# BatteryBoardV3.net
KiCad netlist of a schematic drawn in EAGLE
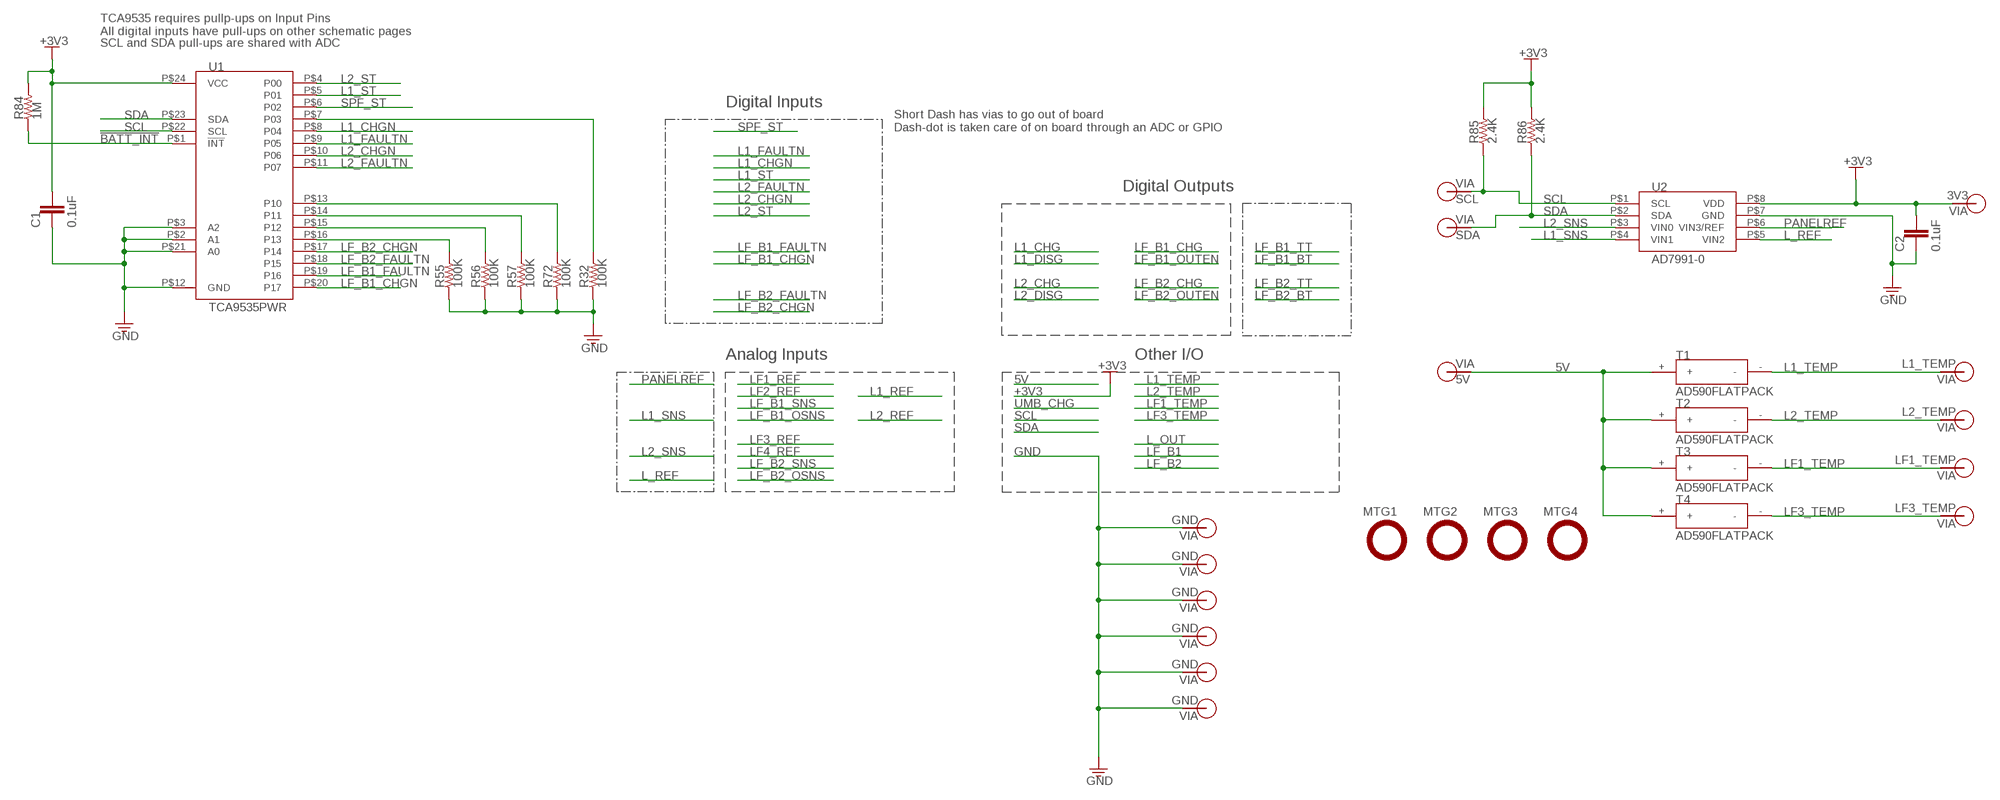
[diagram p0: schematic, sheet 1]
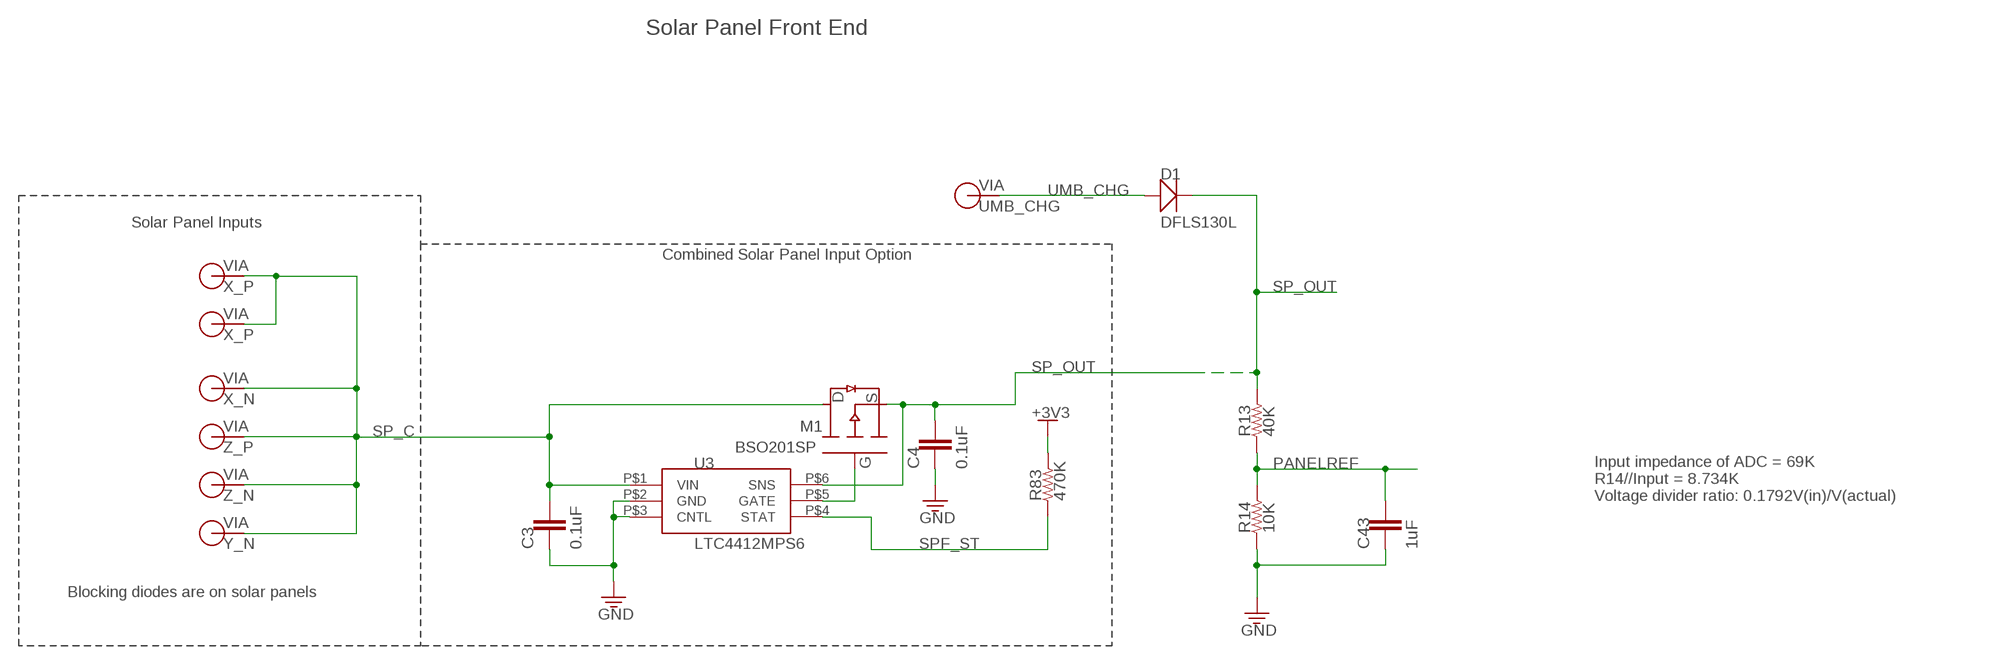
[diagram p1: schematic, sheet 2]
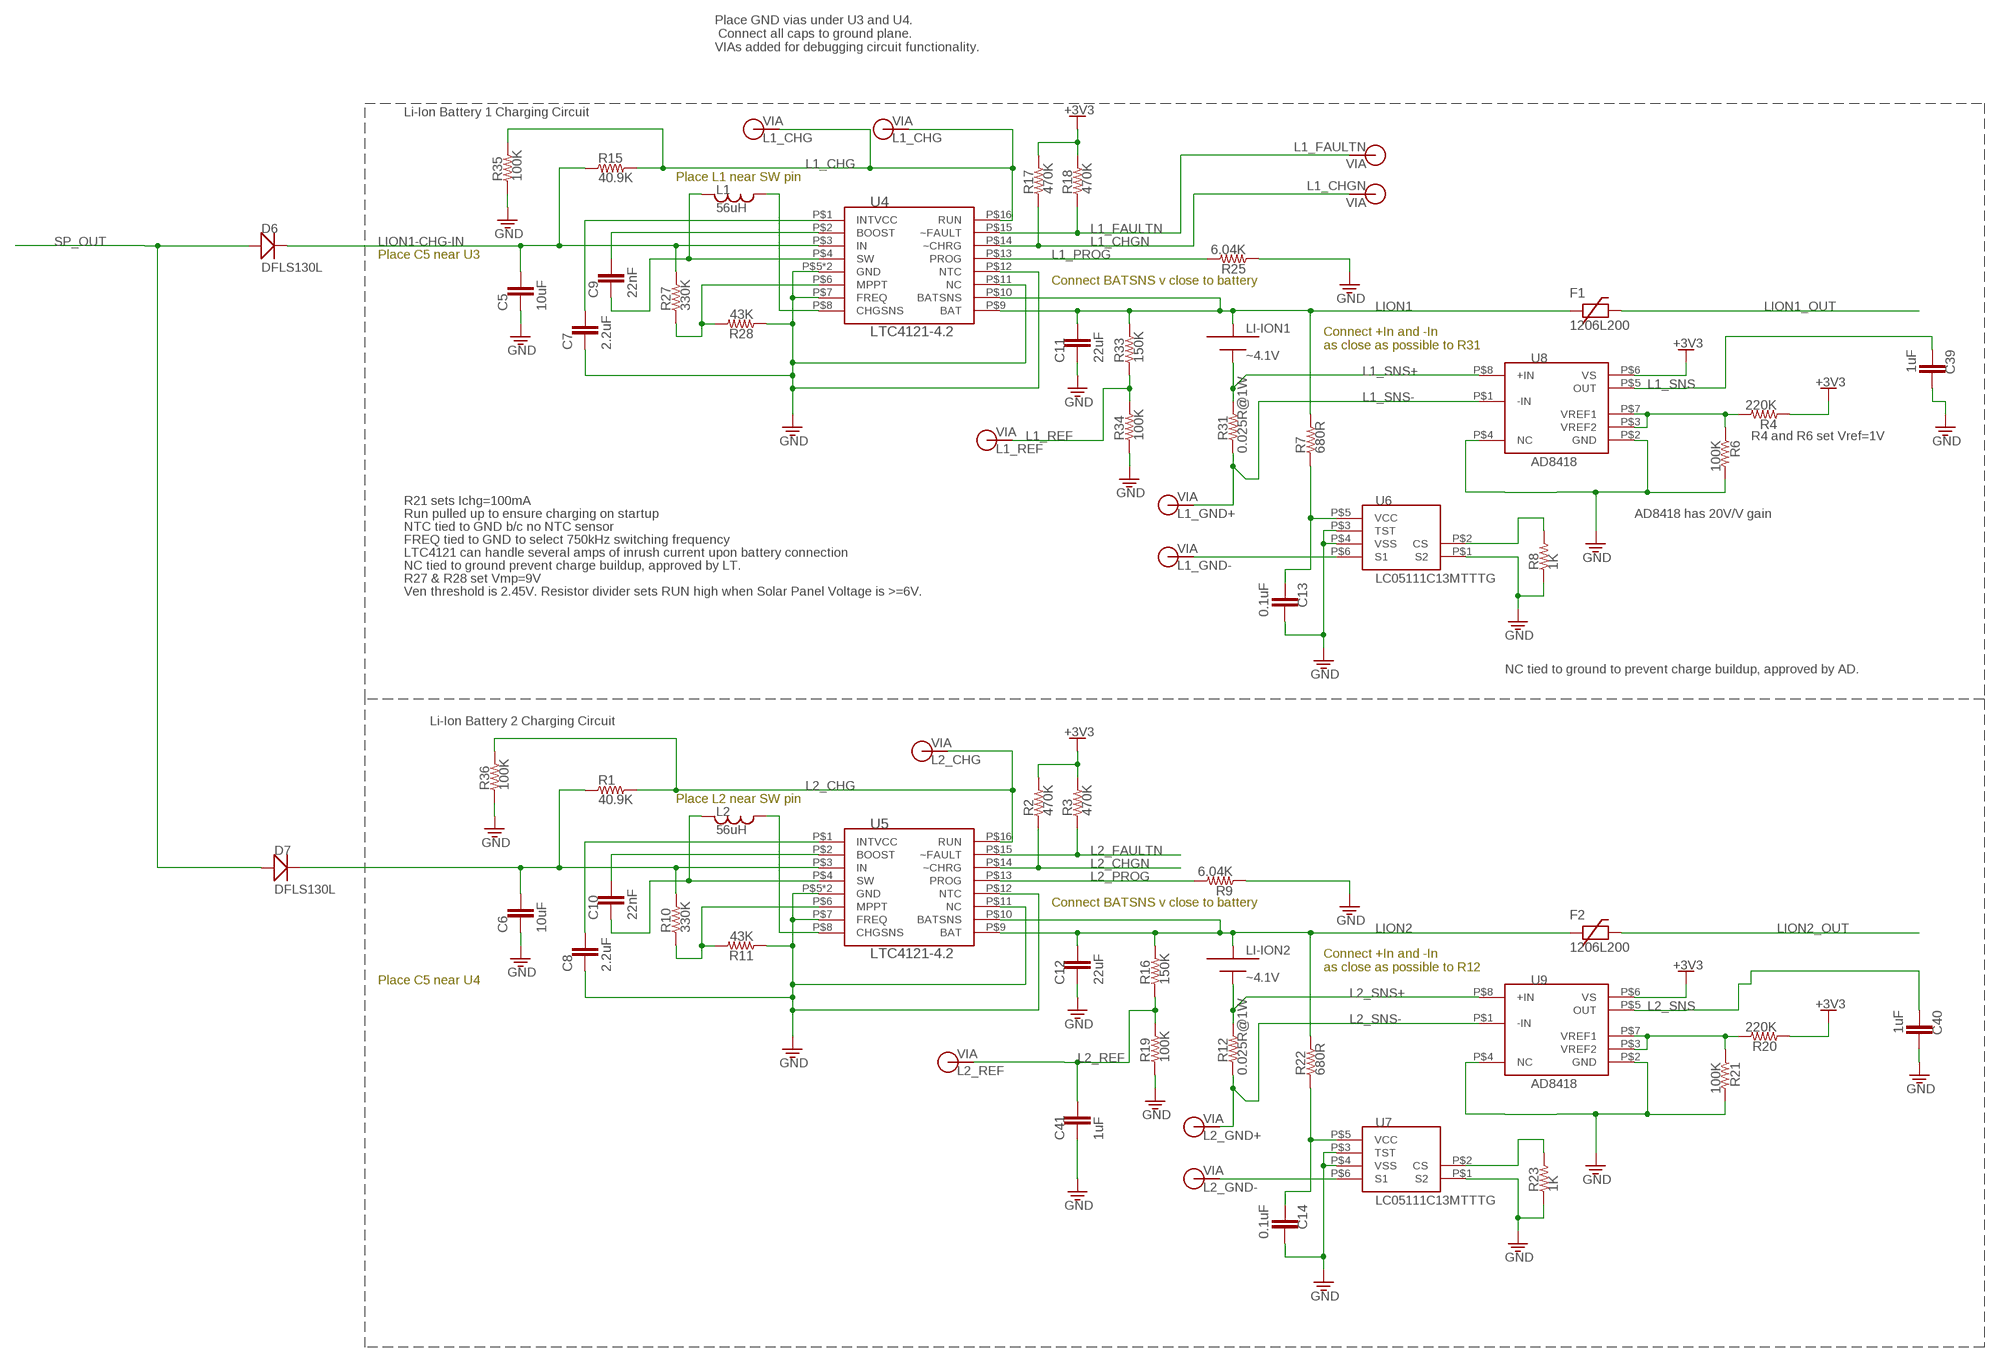
[diagram p2: schematic, sheet 3]
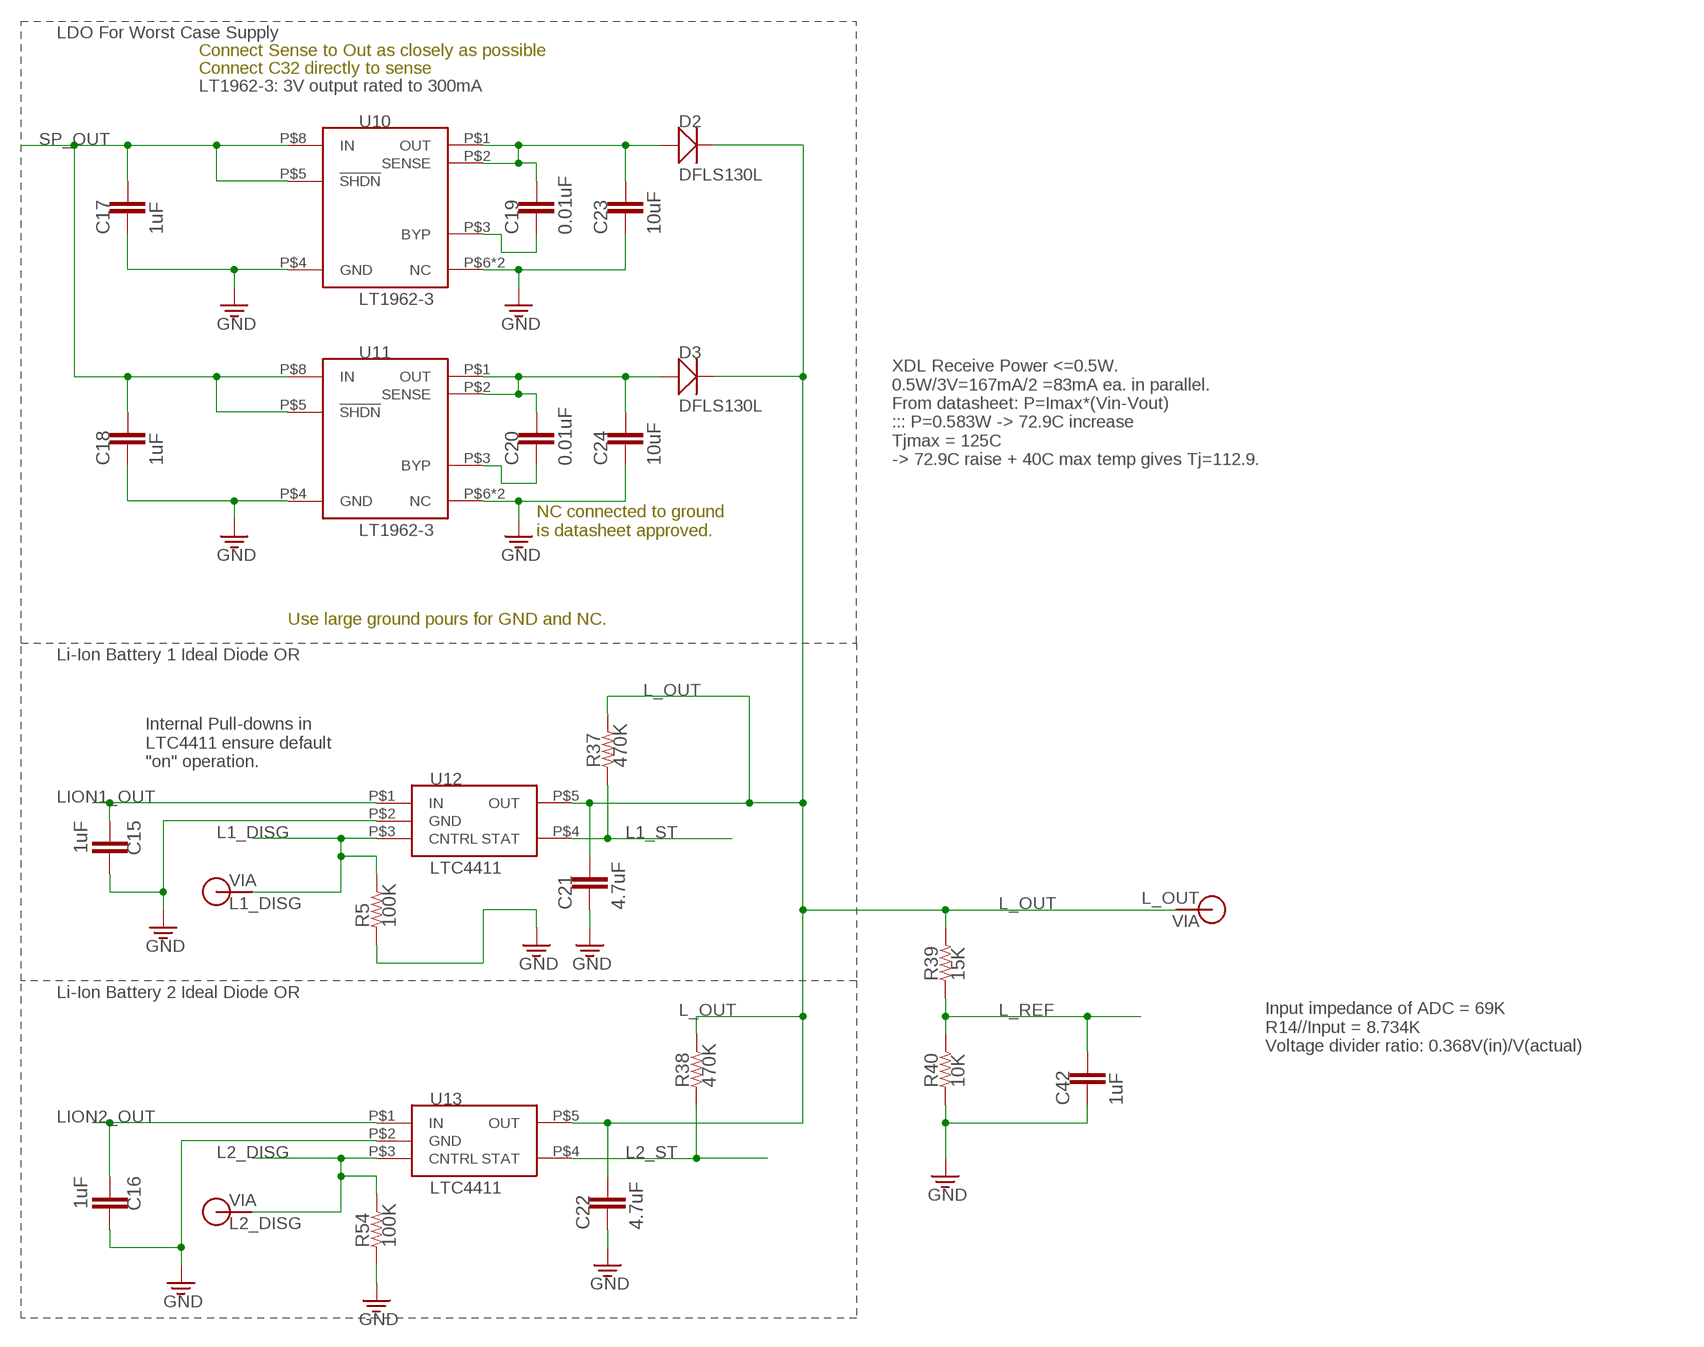
[diagram p3: schematic, sheet 4]
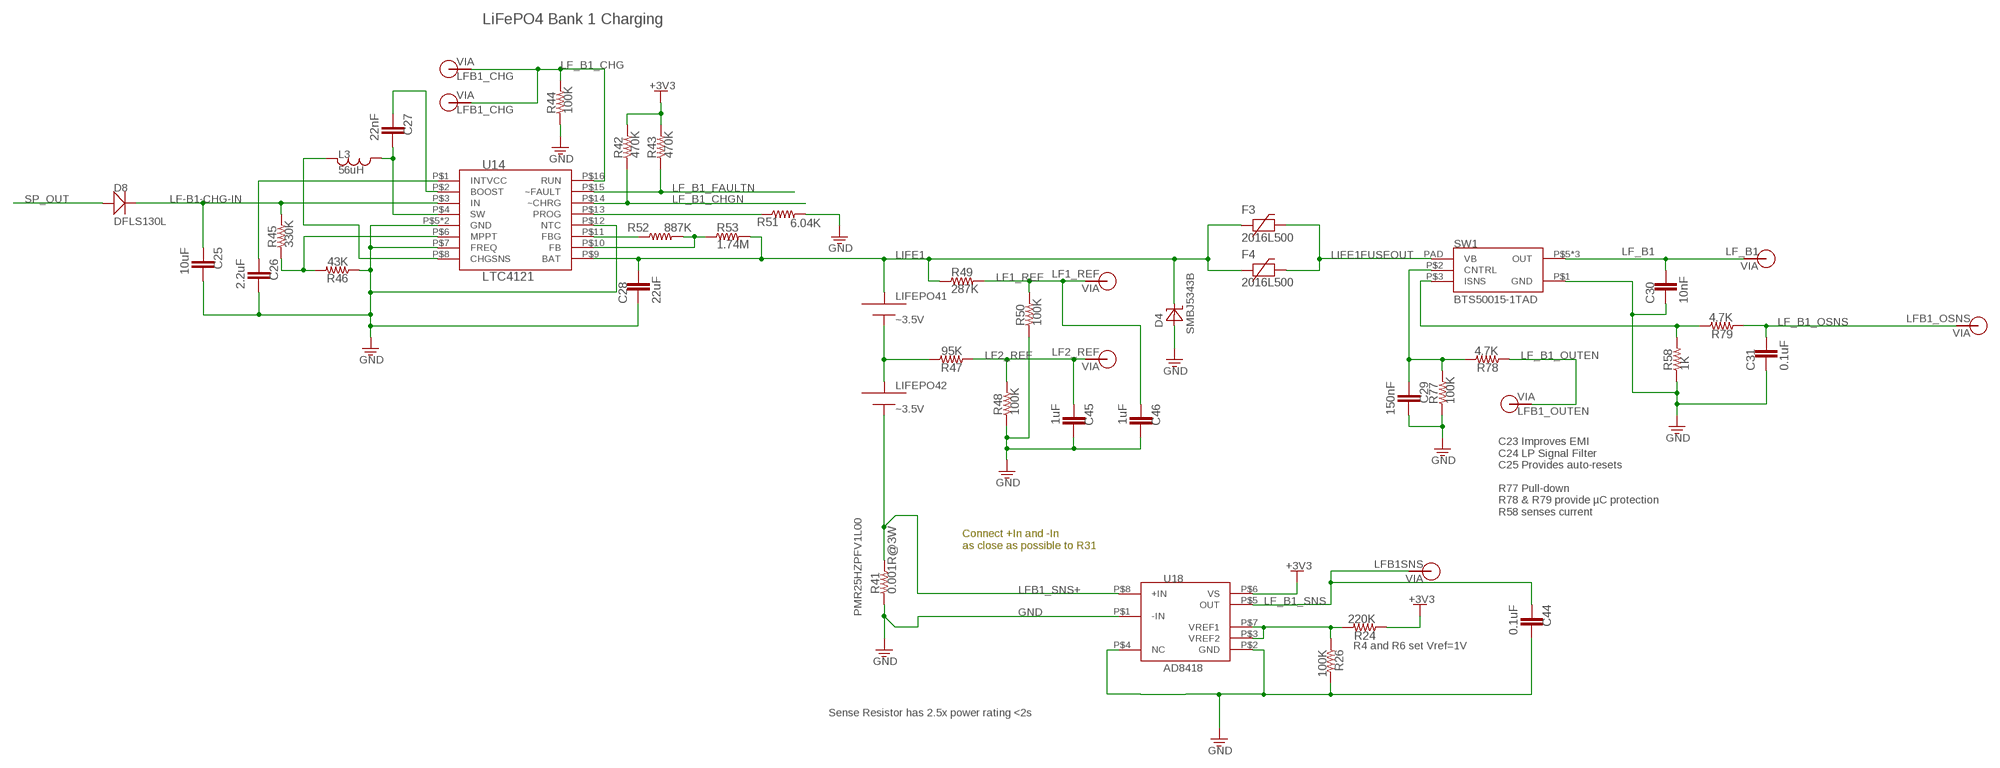
[diagram p4: schematic, sheet 5]
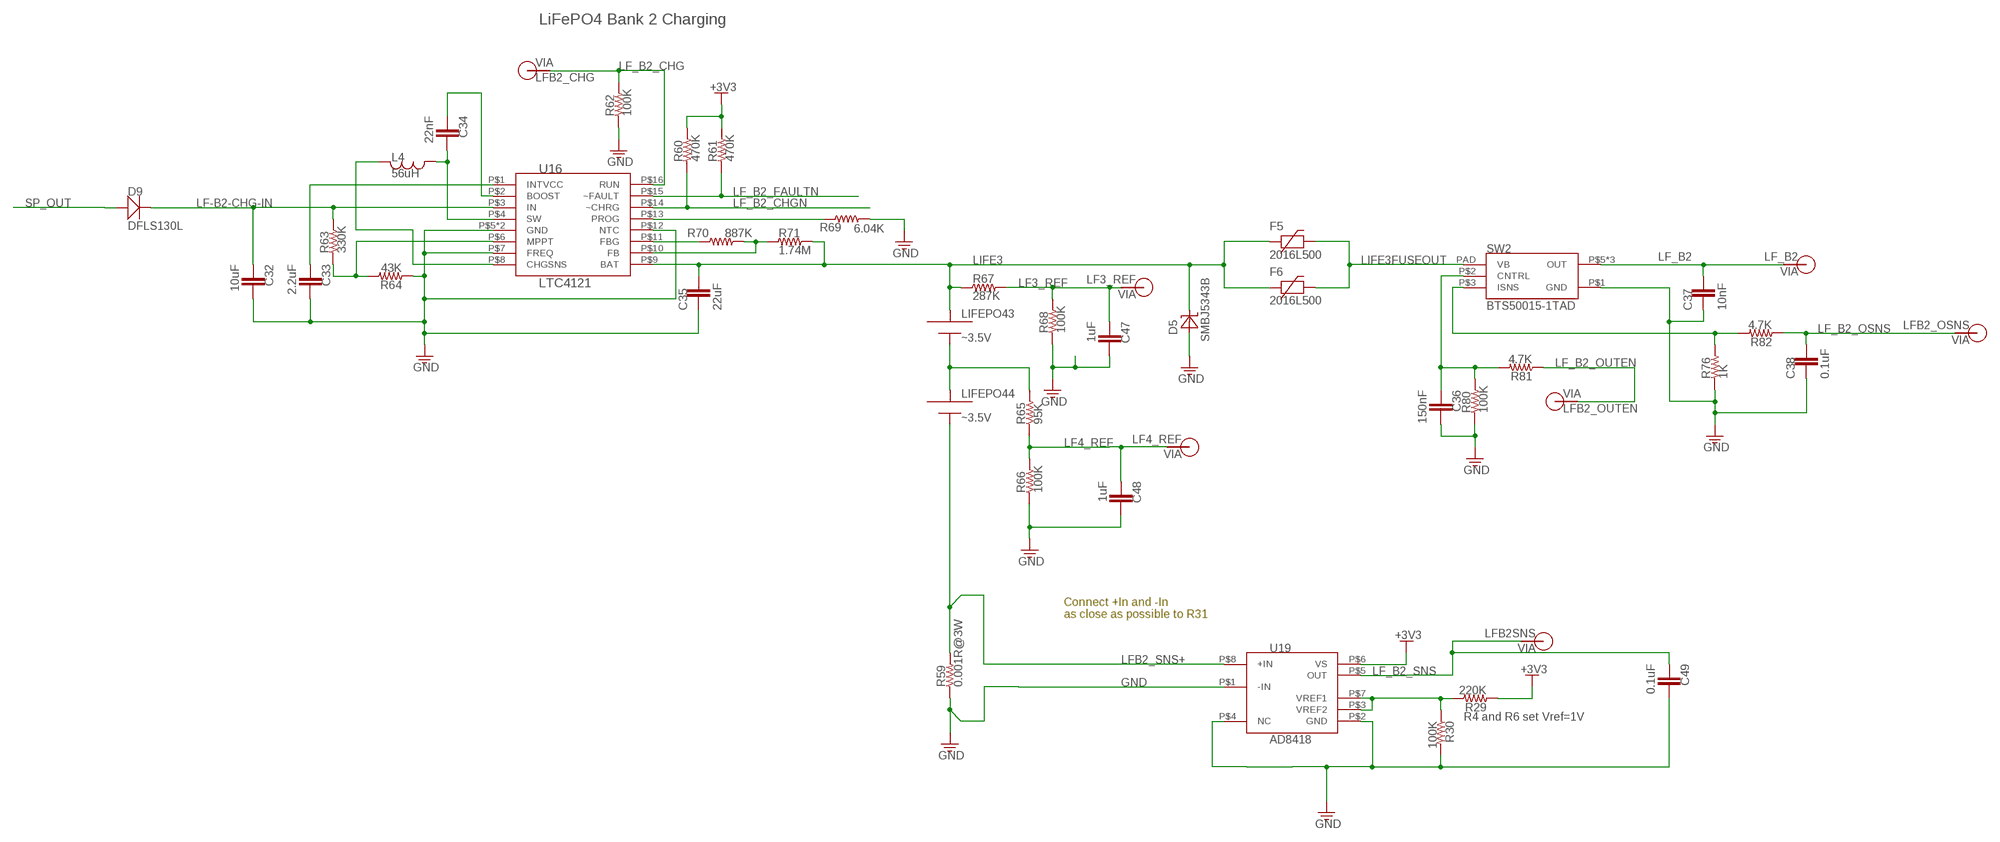
[diagram p5: schematic, sheet 6]

(export (version "E")
  (design (tool "Eeschema 10.0.6"))
  (components
    (comp (ref "C3")
      (value "0.1uF")
      (footprint "eagle-import:0805")
      (libsource (lib "eagle-import") (part "CAP0805"))
    )
    (comp (ref "C4")
      (value "0.1uF")
      (footprint "eagle-import:0805")
      (libsource (lib "eagle-import") (part "CAP0805"))
    )
    (comp (ref "C43")
      (value "1uF")
      (footprint "eagle-import:0805")
      (libsource (lib "eagle-import") (part "CAP0805"))
    )
    (comp (ref "D1")
      (value "DFLS130L")
      (footprint "eagle-import:PWRDI-123")
      (libsource (lib "eagle-import") (part "DFLS130L"))
    )
    (comp (ref "M1")
      (value "BSO201SP")
      (footprint "eagle-import:SO-8")
      (libsource (lib "eagle-import") (part "BSO201SP"))
    )
    (comp (ref "R13")
      (value "40K")
      (footprint "eagle-import:0805")
      (libsource (lib "eagle-import") (part "RES0805"))
    )
    (comp (ref "R14")
      (value "10K")
      (footprint "eagle-import:0805")
      (libsource (lib "eagle-import") (part "RES0805"))
    )
    (comp (ref "R83")
      (value "470K")
      (footprint "eagle-import:0805")
      (libsource (lib "eagle-import") (part "RES0805"))
    )
    (comp (ref "U3")
      (value "LTC4412MPS6")
      (footprint "eagle-import:TSOT23-6")
      (libsource (lib "eagle-import") (part "LTC4412"))
    )
    (comp (ref "V13")
      (value "X_P")
      (footprint "eagle-import:VIA-60MIL")
      (libsource (lib "eagle-import") (part "VIA-60MIL"))
    )
    (comp (ref "V14")
      (value "X_P")
      (footprint "eagle-import:VIA-60MIL-SQ")
      (libsource (lib "eagle-import") (part "VIA60MIL-SQ"))
    )
    (comp (ref "V15")
      (value "X_N")
      (footprint "eagle-import:VIA-60MIL")
      (libsource (lib "eagle-import") (part "VIA-60MIL"))
    )
    (comp (ref "V16")
      (value "Z_P")
      (footprint "eagle-import:VIA-60MIL")
      (libsource (lib "eagle-import") (part "VIA-60MIL"))
    )
    (comp (ref "V17")
      (value "Z_N")
      (footprint "eagle-import:VIA-60MIL")
      (libsource (lib "eagle-import") (part "VIA-60MIL"))
    )
    (comp (ref "V18")
      (value "Y_N")
      (footprint "eagle-import:VIA-60MIL")
      (libsource (lib "eagle-import") (part "VIA-60MIL"))
    )
    (comp (ref "V19")
      (value "UMB_CHG")
      (footprint "eagle-import:VIA-60MIL")
      (libsource (lib "eagle-import") (part "VIA-60MIL"))
    )
    (comp (ref "C1")
      (value "0.1uF")
      (footprint "eagle-import:0805")
      (libsource (lib "eagle-import") (part "CAP0805"))
    )
    (comp (ref "C2")
      (value "0.1uF")
      (footprint "eagle-import:0805")
      (libsource (lib "eagle-import") (part "CAP0805"))
    )
    (comp (ref "MTG1")
      (value "MTG-NPTH-#2-CLOSE")
      (footprint "eagle-import:#2-CLOSE-NPTH")
      (libsource (lib "eagle-import") (part "MTG-NPTH-#2-CLOSE"))
    )
    (comp (ref "MTG2")
      (value "MTG-NPTH-#2-CLOSE")
      (footprint "eagle-import:#2-CLOSE-NPTH")
      (libsource (lib "eagle-import") (part "MTG-NPTH-#2-CLOSE"))
    )
    (comp (ref "MTG3")
      (value "MTG-NPTH-#2-CLOSE")
      (footprint "eagle-import:#2-CLOSE-NPTH")
      (libsource (lib "eagle-import") (part "MTG-NPTH-#2-CLOSE"))
    )
    (comp (ref "MTG4")
      (value "MTG-NPTH-#2-CLOSE")
      (footprint "eagle-import:#2-CLOSE-NPTH")
      (libsource (lib "eagle-import") (part "MTG-NPTH-#2-CLOSE"))
    )
    (comp (ref "R32")
      (value "100K")
      (footprint "eagle-import:0805")
      (libsource (lib "eagle-import") (part "RES0805"))
    )
    (comp (ref "R55")
      (value "100K")
      (footprint "eagle-import:0805")
      (libsource (lib "eagle-import") (part "RES0805"))
    )
    (comp (ref "R56")
      (value "100K")
      (footprint "eagle-import:0805")
      (libsource (lib "eagle-import") (part "RES0805"))
    )
    (comp (ref "R57")
      (value "100K")
      (footprint "eagle-import:0805")
      (libsource (lib "eagle-import") (part "RES0805"))
    )
    (comp (ref "R72")
      (value "100K")
      (footprint "eagle-import:0805")
      (libsource (lib "eagle-import") (part "RES0805"))
    )
    (comp (ref "R84")
      (value "1M")
      (footprint "eagle-import:0805")
      (libsource (lib "eagle-import") (part "RES0805"))
    )
    (comp (ref "R85")
      (value "2.4K")
      (footprint "eagle-import:0805")
      (libsource (lib "eagle-import") (part "RES0805"))
    )
    (comp (ref "R86")
      (value "2.4K")
      (footprint "eagle-import:0805")
      (libsource (lib "eagle-import") (part "RES0805"))
    )
    (comp (ref "T1")
      (value "AD590FLATPACK")
      (footprint "eagle-import:FLATPACK")
      (libsource (lib "eagle-import") (part "AD590FLATPACK"))
    )
    (comp (ref "T2")
      (value "AD590FLATPACK")
      (footprint "eagle-import:FLATPACK")
      (libsource (lib "eagle-import") (part "AD590FLATPACK"))
    )
    (comp (ref "T3")
      (value "AD590FLATPACK")
      (footprint "eagle-import:FLATPACK")
      (libsource (lib "eagle-import") (part "AD590FLATPACK"))
    )
    (comp (ref "T4")
      (value "AD590FLATPACK")
      (footprint "eagle-import:FLATPACK")
      (libsource (lib "eagle-import") (part "AD590FLATPACK"))
    )
    (comp (ref "U1")
      (value "TCA9535PWR")
      (footprint "eagle-import:TSSOP-24")
      (libsource (lib "eagle-import") (part "TCA9535PWR"))
    )
    (comp (ref "U2")
      (value "AD7991-0")
      (footprint "eagle-import:SOT-23-8")
      (libsource (lib "eagle-import") (part "AD7991-0"))
    )
    (comp (ref "V1")
      (value "GND")
      (footprint "eagle-import:VIA-120MIL")
      (libsource (lib "eagle-import") (part "VIA-120MIL"))
    )
    (comp (ref "V2")
      (value "GND")
      (footprint "eagle-import:VIA-120MIL")
      (libsource (lib "eagle-import") (part "VIA-120MIL"))
    )
    (comp (ref "V3")
      (value "GND")
      (footprint "eagle-import:VIA-60MIL-SQ")
      (libsource (lib "eagle-import") (part "VIA60MIL-SQ"))
    )
    (comp (ref "V4")
      (value "GND")
      (footprint "eagle-import:VIA-120MIL")
      (libsource (lib "eagle-import") (part "VIA-120MIL"))
    )
    (comp (ref "V5")
      (value "SCL")
      (footprint "eagle-import:VIA-60MIL")
      (libsource (lib "eagle-import") (part "VIA-60MIL"))
    )
    (comp (ref "V6")
      (value "SDA")
      (footprint "eagle-import:VIA-60MIL")
      (libsource (lib "eagle-import") (part "VIA-60MIL"))
    )
    (comp (ref "V7")
      (value "5V")
      (footprint "eagle-import:VIA-60MIL")
      (libsource (lib "eagle-import") (part "VIA-60MIL"))
    )
    (comp (ref "V8")
      (value "L1_TEMP")
      (footprint "eagle-import:VIA-60MIL")
      (libsource (lib "eagle-import") (part "VIA-60MIL"))
    )
    (comp (ref "V9")
      (value "L2_TEMP")
      (footprint "eagle-import:VIA-60MIL")
      (libsource (lib "eagle-import") (part "VIA-60MIL"))
    )
    (comp (ref "V10")
      (value "LF1_TEMP")
      (footprint "eagle-import:VIA-60MIL")
      (libsource (lib "eagle-import") (part "VIA-60MIL"))
    )
    (comp (ref "V11")
      (value "LF3_TEMP")
      (footprint "eagle-import:VIA-60MIL")
      (libsource (lib "eagle-import") (part "VIA-60MIL"))
    )
    (comp (ref "V12")
      (value "3V3")
      (footprint "eagle-import:VIA-60MIL")
      (libsource (lib "eagle-import") (part "VIA-60MIL"))
    )
    (comp (ref "V28")
      (value "GND")
      (footprint "eagle-import:VIA-60MIL-SQ")
      (libsource (lib "eagle-import") (part "VIA60MIL-SQ"))
    )
    (comp (ref "V36")
      (value "GND")
      (footprint "eagle-import:VIA-60MIL-SQ")
      (libsource (lib "eagle-import") (part "VIA60MIL-SQ"))
    )
    (comp (ref "C25")
      (value "10uF")
      (footprint "eagle-import:0805")
      (libsource (lib "eagle-import") (part "CAP0805"))
    )
    (comp (ref "C26")
      (value "2.2uF")
      (footprint "eagle-import:0805")
      (libsource (lib "eagle-import") (part "CAP0805"))
    )
    (comp (ref "C27")
      (value "22nF")
      (footprint "eagle-import:0805")
      (libsource (lib "eagle-import") (part "CAP0805"))
    )
    (comp (ref "C28")
      (value "22uF")
      (footprint "eagle-import:0805")
      (libsource (lib "eagle-import") (part "CAP0805"))
    )
    (comp (ref "C29")
      (value "150nF")
      (footprint "eagle-import:0805")
      (libsource (lib "eagle-import") (part "CAP0805"))
    )
    (comp (ref "C30")
      (value "10nF")
      (footprint "eagle-import:0805")
      (libsource (lib "eagle-import") (part "CAP0805"))
    )
    (comp (ref "C31")
      (value "0.1uF")
      (footprint "eagle-import:0805")
      (libsource (lib "eagle-import") (part "CAP0805"))
    )
    (comp (ref "C44")
      (value "0.1uF")
      (footprint "eagle-import:0805")
      (libsource (lib "eagle-import") (part "CAP0805"))
    )
    (comp (ref "C45")
      (value "1uF")
      (footprint "eagle-import:0805")
      (libsource (lib "eagle-import") (part "CAP0805"))
    )
    (comp (ref "C46")
      (value "1uF")
      (footprint "eagle-import:0805")
      (libsource (lib "eagle-import") (part "CAP0805"))
    )
    (comp (ref "D4")
      (value "SMBJ5343B")
      (footprint "eagle-import:DO214AA")
      (libsource (lib "eagle-import") (part "SMBJ5343B"))
    )
    (comp (ref "D8")
      (value "DFLS130L")
      (footprint "eagle-import:PWRDI-123")
      (libsource (lib "eagle-import") (part "DFLS130L"))
    )
    (comp (ref "F3")
      (value "2016L500")
      (footprint "eagle-import:2016")
      (libsource (lib "eagle-import") (part "2016L500"))
    )
    (comp (ref "F4")
      (value "2016L500")
      (footprint "eagle-import:2016")
      (libsource (lib "eagle-import") (part "2016L500"))
    )
    (comp (ref "L3")
      (value "56uH")
      (footprint "eagle-import:1812")
      (libsource (lib "eagle-import") (part "IND1812"))
    )
    (comp (ref "LIFEPO41")
      (value "~3.5V")
      (footprint "eagle-import:EQUISAT-BATTERY-VA")
      (libsource (lib "eagle-import") (part "LIFEPO4VA"))
    )
    (comp (ref "LIFEPO42")
      (value "~3.5V")
      (footprint "eagle-import:EQUISAT-BATTERY-VB")
      (libsource (lib "eagle-import") (part "LIFEPO4VB"))
    )
    (comp (ref "R24")
      (value "220K")
      (footprint "eagle-import:0805")
      (libsource (lib "eagle-import") (part "RES0805"))
    )
    (comp (ref "R26")
      (value "100K")
      (footprint "eagle-import:0805")
      (libsource (lib "eagle-import") (part "RES0805"))
    )
    (comp (ref "R41")
      (value "0.001R@3W")
      (footprint "eagle-import:1216")
      (libsource (lib "eagle-import") (part "RES"))
    )
    (comp (ref "R42")
      (value "470K")
      (footprint "eagle-import:0805")
      (libsource (lib "eagle-import") (part "RES0805"))
    )
    (comp (ref "R43")
      (value "470K")
      (footprint "eagle-import:0805")
      (libsource (lib "eagle-import") (part "RES0805"))
    )
    (comp (ref "R44")
      (value "100K")
      (footprint "eagle-import:0805")
      (libsource (lib "eagle-import") (part "RES0805"))
    )
    (comp (ref "R45")
      (value "330K")
      (footprint "eagle-import:0805")
      (libsource (lib "eagle-import") (part "RES0805"))
    )
    (comp (ref "R46")
      (value "43K")
      (footprint "eagle-import:0805")
      (libsource (lib "eagle-import") (part "RES0805"))
    )
    (comp (ref "R47")
      (value "95K")
      (footprint "eagle-import:0805")
      (libsource (lib "eagle-import") (part "RES0805"))
    )
    (comp (ref "R48")
      (value "100K")
      (footprint "eagle-import:0805")
      (libsource (lib "eagle-import") (part "RES0805"))
    )
    (comp (ref "R49")
      (value "287K")
      (footprint "eagle-import:0805")
      (libsource (lib "eagle-import") (part "RES0805"))
    )
    (comp (ref "R50")
      (value "100K")
      (footprint "eagle-import:0805")
      (libsource (lib "eagle-import") (part "RES0805"))
    )
    (comp (ref "R51")
      (value "6.04K")
      (footprint "eagle-import:0805")
      (libsource (lib "eagle-import") (part "RES0805"))
    )
    (comp (ref "R52")
      (value "887K")
      (footprint "eagle-import:0805")
      (libsource (lib "eagle-import") (part "RES0805"))
    )
    (comp (ref "R53")
      (value "1.74M")
      (footprint "eagle-import:0805")
      (libsource (lib "eagle-import") (part "RES0805"))
    )
    (comp (ref "R58")
      (value "1K")
      (footprint "eagle-import:0805")
      (libsource (lib "eagle-import") (part "RES0805"))
    )
    (comp (ref "R77")
      (value "100K")
      (footprint "eagle-import:0805")
      (libsource (lib "eagle-import") (part "RES0805"))
    )
    (comp (ref "R78")
      (value "4.7K")
      (footprint "eagle-import:0805")
      (libsource (lib "eagle-import") (part "RES0805"))
    )
    (comp (ref "R79")
      (value "4.7K")
      (footprint "eagle-import:0805")
      (libsource (lib "eagle-import") (part "RES0805"))
    )
    (comp (ref "SW1")
      (value "BTS50015-1TAD")
      (footprint "eagle-import:TO-263-7-8")
      (libsource (lib "eagle-import") (part "BTS50015-1TAD"))
    )
    (comp (ref "U14")
      (value "LTC4121")
      (footprint "eagle-import:QFN-16-PAD")
      (libsource (lib "eagle-import") (part "LTC4121"))
    )
    (comp (ref "U18")
      (value "AD8418")
      (footprint "eagle-import:MSOP-8")
      (libsource (lib "eagle-import") (part "AD8418"))
    )
    (comp (ref "V32")
      (value "LFB1_CHG")
      (footprint "eagle-import:VIA-60MIL-SQ")
      (libsource (lib "eagle-import") (part "VIA60MIL-SQ"))
    )
    (comp (ref "V35")
      (value "LFB1_CHG")
      (footprint "eagle-import:VIA-60MIL")
      (libsource (lib "eagle-import") (part "VIA-60MIL"))
    )
    (comp (ref "V40")
      (value "LFB1SNS")
      (footprint "eagle-import:VIA-60MIL")
      (libsource (lib "eagle-import") (part "VIA-60MIL"))
    )
    (comp (ref "V41")
      (value "LF1_REF")
      (footprint "eagle-import:VIA-60MIL")
      (libsource (lib "eagle-import") (part "VIA-60MIL"))
    )
    (comp (ref "V42")
      (value "LF2_REF")
      (footprint "eagle-import:VIA-60MIL")
      (libsource (lib "eagle-import") (part "VIA-60MIL"))
    )
    (comp (ref "V43")
      (value "LFB1_OUTEN")
      (footprint "eagle-import:VIA-60MIL")
      (libsource (lib "eagle-import") (part "VIA-60MIL"))
    )
    (comp (ref "V45")
      (value "LF_B1")
      (footprint "eagle-import:VIA-120MIL")
      (libsource (lib "eagle-import") (part "VIA-120MIL"))
    )
    (comp (ref "V46")
      (value "LFB1_OSNS")
      (footprint "eagle-import:VIA-60MIL")
      (libsource (lib "eagle-import") (part "VIA-60MIL"))
    )
    (comp (ref "C5")
      (value "10uF")
      (footprint "eagle-import:0805")
      (libsource (lib "eagle-import") (part "CAP0805"))
    )
    (comp (ref "C6")
      (value "10uF")
      (footprint "eagle-import:0805")
      (libsource (lib "eagle-import") (part "CAP0805"))
    )
    (comp (ref "C7")
      (value "2.2uF")
      (footprint "eagle-import:0805")
      (libsource (lib "eagle-import") (part "CAP0805"))
    )
    (comp (ref "C8")
      (value "2.2uF")
      (footprint "eagle-import:0805")
      (libsource (lib "eagle-import") (part "CAP0805"))
    )
    (comp (ref "C9")
      (value "22nF")
      (footprint "eagle-import:0805")
      (libsource (lib "eagle-import") (part "CAP0805"))
    )
    (comp (ref "C10")
      (value "22nF")
      (footprint "eagle-import:0805")
      (libsource (lib "eagle-import") (part "CAP0805"))
    )
    (comp (ref "C11")
      (value "22uF")
      (footprint "eagle-import:0805")
      (libsource (lib "eagle-import") (part "CAP0805"))
    )
    (comp (ref "C12")
      (value "22uF")
      (footprint "eagle-import:0805")
      (libsource (lib "eagle-import") (part "CAP0805"))
    )
    (comp (ref "C13")
      (value "0.1uF")
      (footprint "eagle-import:0805")
      (libsource (lib "eagle-import") (part "CAP0805"))
    )
    (comp (ref "C14")
      (value "0.1uF")
      (footprint "eagle-import:0805")
      (libsource (lib "eagle-import") (part "CAP0805"))
    )
    (comp (ref "C39")
      (value "1uF")
      (footprint "eagle-import:0805")
      (libsource (lib "eagle-import") (part "CAP0805"))
    )
    (comp (ref "C40")
      (value "1uF")
      (footprint "eagle-import:0805")
      (libsource (lib "eagle-import") (part "CAP0805"))
    )
    (comp (ref "C41")
      (value "1uF")
      (footprint "eagle-import:0805")
      (libsource (lib "eagle-import") (part "CAP0805"))
    )
    (comp (ref "D6")
      (value "DFLS130L")
      (footprint "eagle-import:PWRDI-123")
      (libsource (lib "eagle-import") (part "DFLS130L"))
    )
    (comp (ref "D7")
      (value "DFLS130L")
      (footprint "eagle-import:PWRDI-123")
      (libsource (lib "eagle-import") (part "DFLS130L"))
    )
    (comp (ref "F1")
      (value "1206L200")
      (footprint "eagle-import:1206")
      (libsource (lib "eagle-import") (part "PTCFUSE1206"))
    )
    (comp (ref "F2")
      (value "1206L200")
      (footprint "eagle-import:1206")
      (libsource (lib "eagle-import") (part "PTCFUSE1206"))
    )
    (comp (ref "L1")
      (value "56uH")
      (footprint "eagle-import:1812")
      (libsource (lib "eagle-import") (part "IND1812"))
    )
    (comp (ref "L2")
      (value "56uH")
      (footprint "eagle-import:1812")
      (libsource (lib "eagle-import") (part "IND1812"))
    )
    (comp (ref "LI-ION1")
      (value "~4.1V")
      (footprint "eagle-import:EQUISAT-BATTERY-VA")
      (libsource (lib "eagle-import") (part "LI-ION"))
    )
    (comp (ref "LI-ION2")
      (value "~4.1V")
      (footprint "eagle-import:EQUISAT-BATTERY-VA")
      (libsource (lib "eagle-import") (part "LI-ION"))
    )
    (comp (ref "R1")
      (value "40.9K")
      (footprint "eagle-import:0805")
      (libsource (lib "eagle-import") (part "RES0805"))
    )
    (comp (ref "R2")
      (value "470K")
      (footprint "eagle-import:0805")
      (libsource (lib "eagle-import") (part "RES0805"))
    )
    (comp (ref "R3")
      (value "470K")
      (footprint "eagle-import:0805")
      (libsource (lib "eagle-import") (part "RES0805"))
    )
    (comp (ref "R4")
      (value "220K")
      (footprint "eagle-import:0805")
      (libsource (lib "eagle-import") (part "RES0805"))
    )
    (comp (ref "R6")
      (value "100K")
      (footprint "eagle-import:0805")
      (libsource (lib "eagle-import") (part "RES0805"))
    )
    (comp (ref "R7")
      (value "680R")
      (footprint "eagle-import:0805")
      (libsource (lib "eagle-import") (part "RES0805"))
    )
    (comp (ref "R8")
      (value "1K")
      (footprint "eagle-import:0805")
      (libsource (lib "eagle-import") (part "RES0805"))
    )
    (comp (ref "R9")
      (value "6.04K")
      (footprint "eagle-import:0805")
      (libsource (lib "eagle-import") (part "RES0805"))
    )
    (comp (ref "R10")
      (value "330K")
      (footprint "eagle-import:0805")
      (libsource (lib "eagle-import") (part "RES0805"))
    )
    (comp (ref "R11")
      (value "43K")
      (footprint "eagle-import:0805")
      (libsource (lib "eagle-import") (part "RES0805"))
    )
    (comp (ref "R12")
      (value "0.025R@1W")
      (footprint "eagle-import:1210")
      (libsource (lib "eagle-import") (part "RES1210"))
    )
    (comp (ref "R15")
      (value "40.9K")
      (footprint "eagle-import:0805")
      (libsource (lib "eagle-import") (part "RES0805"))
    )
    (comp (ref "R16")
      (value "150K")
      (footprint "eagle-import:0805")
      (libsource (lib "eagle-import") (part "RES0805"))
    )
    (comp (ref "R17")
      (value "470K")
      (footprint "eagle-import:0805")
      (libsource (lib "eagle-import") (part "RES0805"))
    )
    (comp (ref "R18")
      (value "470K")
      (footprint "eagle-import:0805")
      (libsource (lib "eagle-import") (part "RES0805"))
    )
    (comp (ref "R19")
      (value "100K")
      (footprint "eagle-import:0805")
      (libsource (lib "eagle-import") (part "RES0805"))
    )
    (comp (ref "R20")
      (value "220K")
      (footprint "eagle-import:0805")
      (libsource (lib "eagle-import") (part "RES0805"))
    )
    (comp (ref "R21")
      (value "100K")
      (footprint "eagle-import:0805")
      (libsource (lib "eagle-import") (part "RES0805"))
    )
    (comp (ref "R22")
      (value "680R")
      (footprint "eagle-import:0805")
      (libsource (lib "eagle-import") (part "RES0805"))
    )
    (comp (ref "R23")
      (value "1K")
      (footprint "eagle-import:0805")
      (libsource (lib "eagle-import") (part "RES0805"))
    )
    (comp (ref "R25")
      (value "6.04K")
      (footprint "eagle-import:0805")
      (libsource (lib "eagle-import") (part "RES0805"))
    )
    (comp (ref "R27")
      (value "330K")
      (footprint "eagle-import:0805")
      (libsource (lib "eagle-import") (part "RES0805"))
    )
    (comp (ref "R28")
      (value "43K")
      (footprint "eagle-import:0805")
      (libsource (lib "eagle-import") (part "RES0805"))
    )
    (comp (ref "R31")
      (value "0.025R@1W")
      (footprint "eagle-import:1210")
      (libsource (lib "eagle-import") (part "RES1210"))
    )
    (comp (ref "R33")
      (value "150K")
      (footprint "eagle-import:0805")
      (libsource (lib "eagle-import") (part "RES0805"))
    )
    (comp (ref "R34")
      (value "100K")
      (footprint "eagle-import:0805")
      (libsource (lib "eagle-import") (part "RES0805"))
    )
    (comp (ref "R35")
      (value "100K")
      (footprint "eagle-import:0805")
      (libsource (lib "eagle-import") (part "RES0805"))
    )
    (comp (ref "R36")
      (value "100K")
      (footprint "eagle-import:0805")
      (libsource (lib "eagle-import") (part "RES0805"))
    )
    (comp (ref "U4")
      (value "LTC4121-4.2")
      (footprint "eagle-import:QFN-16-PAD")
      (libsource (lib "eagle-import") (part "LTC4121-4.2"))
    )
    (comp (ref "U5")
      (value "LTC4121-4.2")
      (footprint "eagle-import:QFN-16-PAD")
      (libsource (lib "eagle-import") (part "LTC4121-4.2"))
    )
    (comp (ref "U6")
      (value "LC05111C13MTTTG")
      (footprint "eagle-import:WDFN6")
      (libsource (lib "eagle-import") (part "LC05111C13MTTTG"))
    )
    (comp (ref "U7")
      (value "LC05111C13MTTTG")
      (footprint "eagle-import:WDFN6")
      (libsource (lib "eagle-import") (part "LC05111C13MTTTG"))
    )
    (comp (ref "U8")
      (value "AD8418")
      (footprint "eagle-import:MSOP-8")
      (libsource (lib "eagle-import") (part "AD8418"))
    )
    (comp (ref "U9")
      (value "AD8418")
      (footprint "eagle-import:MSOP-8")
      (libsource (lib "eagle-import") (part "AD8418"))
    )
    (comp (ref "V20")
      (value "L1_CHG")
      (footprint "eagle-import:VIA-60MIL")
      (libsource (lib "eagle-import") (part "VIA-60MIL"))
    )
    (comp (ref "V21")
      (value "L1_REF")
      (footprint "eagle-import:VIA-60MIL")
      (libsource (lib "eagle-import") (part "VIA-60MIL"))
    )
    (comp (ref "V22")
      (value "L1_GND+")
      (footprint "eagle-import:VIA-60MIL")
      (libsource (lib "eagle-import") (part "VIA-60MIL"))
    )
    (comp (ref "V23")
      (value "L1_GND-")
      (footprint "eagle-import:VIA-60MIL")
      (libsource (lib "eagle-import") (part "VIA-60MIL"))
    )
    (comp (ref "V24")
      (value "L2_GND+")
      (footprint "eagle-import:VIA-60MIL")
      (libsource (lib "eagle-import") (part "VIA-60MIL"))
    )
    (comp (ref "V25")
      (value "L2_GND-")
      (footprint "eagle-import:VIA-60MIL")
      (libsource (lib "eagle-import") (part "VIA-60MIL"))
    )
    (comp (ref "V26")
      (value "L1_FAULTN")
      (footprint "eagle-import:VIA-60MIL-SQ")
      (libsource (lib "eagle-import") (part "VIA60MIL-SQ"))
    )
    (comp (ref "V27")
      (value "L1_CHGN")
      (footprint "eagle-import:VIA-60MIL-SQ")
      (libsource (lib "eagle-import") (part "VIA60MIL-SQ"))
    )
    (comp (ref "V31")
      (value "L2_REF")
      (footprint "eagle-import:VIA-60MIL")
      (libsource (lib "eagle-import") (part "VIA-60MIL"))
    )
    (comp (ref "V33")
      (value "L2_CHG")
      (footprint "eagle-import:VIA-60MIL")
      (libsource (lib "eagle-import") (part "VIA-60MIL"))
    )
    (comp (ref "V48")
      (value "L1_CHG")
      (footprint "eagle-import:VIA-60MIL-SQ")
      (libsource (lib "eagle-import") (part "VIA60MIL-SQ"))
    )
    (comp (ref "C15")
      (value "1uF")
      (footprint "eagle-import:0805")
      (libsource (lib "eagle-import") (part "CAP0805"))
    )
    (comp (ref "C16")
      (value "1uF")
      (footprint "eagle-import:0805")
      (libsource (lib "eagle-import") (part "CAP0805"))
    )
    (comp (ref "C17")
      (value "1uF")
      (footprint "eagle-import:0805")
      (libsource (lib "eagle-import") (part "CAP0805"))
    )
    (comp (ref "C18")
      (value "1uF")
      (footprint "eagle-import:0805")
      (libsource (lib "eagle-import") (part "CAP0805"))
    )
    (comp (ref "C19")
      (value "0.01uF")
      (footprint "eagle-import:0805")
      (libsource (lib "eagle-import") (part "CAP0805"))
    )
    (comp (ref "C20")
      (value "0.01uF")
      (footprint "eagle-import:0805")
      (libsource (lib "eagle-import") (part "CAP0805"))
    )
    (comp (ref "C21")
      (value "4.7uF")
      (footprint "eagle-import:0805")
      (libsource (lib "eagle-import") (part "CAP0805"))
    )
    (comp (ref "C22")
      (value "4.7uF")
      (footprint "eagle-import:0805")
      (libsource (lib "eagle-import") (part "CAP0805"))
    )
    (comp (ref "C23")
      (value "10uF")
      (footprint "eagle-import:0805")
      (libsource (lib "eagle-import") (part "CAP0805"))
    )
    (comp (ref "C24")
      (value "10uF")
      (footprint "eagle-import:0805")
      (libsource (lib "eagle-import") (part "CAP0805"))
    )
    (comp (ref "C42")
      (value "1uF")
      (footprint "eagle-import:0805")
      (libsource (lib "eagle-import") (part "CAP0805"))
    )
    (comp (ref "D2")
      (value "DFLS130L")
      (footprint "eagle-import:PWRDI-123")
      (libsource (lib "eagle-import") (part "DFLS130L"))
    )
    (comp (ref "D3")
      (value "DFLS130L")
      (footprint "eagle-import:PWRDI-123")
      (libsource (lib "eagle-import") (part "DFLS130L"))
    )
    (comp (ref "R5")
      (value "100K")
      (footprint "eagle-import:0805")
      (libsource (lib "eagle-import") (part "RES0805"))
    )
    (comp (ref "R37")
      (value "470K")
      (footprint "eagle-import:0805")
      (libsource (lib "eagle-import") (part "RES0805"))
    )
    (comp (ref "R38")
      (value "470K")
      (footprint "eagle-import:0805")
      (libsource (lib "eagle-import") (part "RES0805"))
    )
    (comp (ref "R39")
      (value "15K")
      (footprint "eagle-import:0805")
      (libsource (lib "eagle-import") (part "RES0805"))
    )
    (comp (ref "R40")
      (value "10K")
      (footprint "eagle-import:0805")
      (libsource (lib "eagle-import") (part "RES0805"))
    )
    (comp (ref "R54")
      (value "100K")
      (footprint "eagle-import:0805")
      (libsource (lib "eagle-import") (part "RES0805"))
    )
    (comp (ref "U10")
      (value "LT1962-3")
      (footprint "eagle-import:MSOP-8")
      (libsource (lib "eagle-import") (part "LT1962-3"))
    )
    (comp (ref "U11")
      (value "LT1962-3")
      (footprint "eagle-import:MSOP-8")
      (libsource (lib "eagle-import") (part "LT1962-3"))
    )
    (comp (ref "U12")
      (value "LTC4411")
      (footprint "eagle-import:TSOT23-5")
      (libsource (lib "eagle-import") (part "LTC4411"))
    )
    (comp (ref "U13")
      (value "LTC4411")
      (footprint "eagle-import:TSOT23-5")
      (libsource (lib "eagle-import") (part "LTC4411"))
    )
    (comp (ref "V29")
      (value "L1_DISG")
      (footprint "eagle-import:VIA-60MIL")
      (libsource (lib "eagle-import") (part "VIA-60MIL"))
    )
    (comp (ref "V30")
      (value "L2_DISG")
      (footprint "eagle-import:VIA-60MIL")
      (libsource (lib "eagle-import") (part "VIA-60MIL"))
    )
    (comp (ref "V34")
      (value "L_OUT")
      (footprint "eagle-import:VIA-120MIL")
      (libsource (lib "eagle-import") (part "VIA-120MIL"))
    )
    (comp (ref "C32")
      (value "10uF")
      (footprint "eagle-import:0805")
      (libsource (lib "eagle-import") (part "CAP0805"))
    )
    (comp (ref "C33")
      (value "2.2uF")
      (footprint "eagle-import:0805")
      (libsource (lib "eagle-import") (part "CAP0805"))
    )
    (comp (ref "C34")
      (value "22nF")
      (footprint "eagle-import:0805")
      (libsource (lib "eagle-import") (part "CAP0805"))
    )
    (comp (ref "C35")
      (value "22uF")
      (footprint "eagle-import:0805")
      (libsource (lib "eagle-import") (part "CAP0805"))
    )
    (comp (ref "C36")
      (value "150nF")
      (footprint "eagle-import:0805")
      (libsource (lib "eagle-import") (part "CAP0805"))
    )
    (comp (ref "C37")
      (value "10nF")
      (footprint "eagle-import:0805")
      (libsource (lib "eagle-import") (part "CAP0805"))
    )
    (comp (ref "C38")
      (value "0.1uF")
      (footprint "eagle-import:0805")
      (libsource (lib "eagle-import") (part "CAP0805"))
    )
    (comp (ref "C47")
      (value "1uF")
      (footprint "eagle-import:0805")
      (libsource (lib "eagle-import") (part "CAP0805"))
    )
    (comp (ref "C48")
      (value "1uF")
      (footprint "eagle-import:0805")
      (libsource (lib "eagle-import") (part "CAP0805"))
    )
    (comp (ref "C49")
      (value "0.1uF")
      (footprint "eagle-import:0805")
      (libsource (lib "eagle-import") (part "CAP0805"))
    )
    (comp (ref "D5")
      (value "SMBJ5343B")
      (footprint "eagle-import:DO214AA")
      (libsource (lib "eagle-import") (part "SMBJ5343B"))
    )
    (comp (ref "D9")
      (value "DFLS130L")
      (footprint "eagle-import:PWRDI-123")
      (libsource (lib "eagle-import") (part "DFLS130L"))
    )
    (comp (ref "F5")
      (value "2016L500")
      (footprint "eagle-import:2016")
      (libsource (lib "eagle-import") (part "2016L500"))
    )
    (comp (ref "F6")
      (value "2016L500")
      (footprint "eagle-import:2016")
      (libsource (lib "eagle-import") (part "2016L500"))
    )
    (comp (ref "L4")
      (value "56uH")
      (footprint "eagle-import:1812")
      (libsource (lib "eagle-import") (part "IND1812"))
    )
    (comp (ref "LIFEPO43")
      (value "~3.5V")
      (footprint "eagle-import:EQUISAT-BATTERY-VA")
      (libsource (lib "eagle-import") (part "LIFEPO4VA"))
    )
    (comp (ref "LIFEPO44")
      (value "~3.5V")
      (footprint "eagle-import:EQUISAT-BATTERY-VB")
      (libsource (lib "eagle-import") (part "LIFEPO4VB"))
    )
    (comp (ref "R29")
      (value "220K")
      (footprint "eagle-import:0805")
      (libsource (lib "eagle-import") (part "RES0805"))
    )
    (comp (ref "R30")
      (value "100K")
      (footprint "eagle-import:0805")
      (libsource (lib "eagle-import") (part "RES0805"))
    )
    (comp (ref "R59")
      (value "0.001R@3W")
      (footprint "eagle-import:1216")
      (libsource (lib "eagle-import") (part "RES"))
    )
    (comp (ref "R60")
      (value "470K")
      (footprint "eagle-import:0805")
      (libsource (lib "eagle-import") (part "RES0805"))
    )
    (comp (ref "R61")
      (value "470K")
      (footprint "eagle-import:0805")
      (libsource (lib "eagle-import") (part "RES0805"))
    )
    (comp (ref "R62")
      (value "100K")
      (footprint "eagle-import:0805")
      (libsource (lib "eagle-import") (part "RES0805"))
    )
    (comp (ref "R63")
      (value "330K")
      (footprint "eagle-import:0805")
      (libsource (lib "eagle-import") (part "RES0805"))
    )
    (comp (ref "R64")
      (value "43K")
      (footprint "eagle-import:0805")
      (libsource (lib "eagle-import") (part "RES0805"))
    )
    (comp (ref "R65")
      (value "95K")
      (footprint "eagle-import:0805")
      (libsource (lib "eagle-import") (part "RES0805"))
    )
    (comp (ref "R66")
      (value "100K")
      (footprint "eagle-import:0805")
      (libsource (lib "eagle-import") (part "RES0805"))
    )
    (comp (ref "R67")
      (value "287K")
      (footprint "eagle-import:0805")
      (libsource (lib "eagle-import") (part "RES0805"))
    )
    (comp (ref "R68")
      (value "100K")
      (footprint "eagle-import:0805")
      (libsource (lib "eagle-import") (part "RES0805"))
    )
    (comp (ref "R69")
      (value "6.04K")
      (footprint "eagle-import:0805")
      (libsource (lib "eagle-import") (part "RES0805"))
    )
    (comp (ref "R70")
      (value "887K")
      (footprint "eagle-import:0805")
      (libsource (lib "eagle-import") (part "RES0805"))
    )
    (comp (ref "R71")
      (value "1.74M")
      (footprint "eagle-import:0805")
      (libsource (lib "eagle-import") (part "RES0805"))
    )
    (comp (ref "R76")
      (value "1K")
      (footprint "eagle-import:0805")
      (libsource (lib "eagle-import") (part "RES0805"))
    )
    (comp (ref "R80")
      (value "100K")
      (footprint "eagle-import:0805")
      (libsource (lib "eagle-import") (part "RES0805"))
    )
    (comp (ref "R81")
      (value "4.7K")
      (footprint "eagle-import:0805")
      (libsource (lib "eagle-import") (part "RES0805"))
    )
    (comp (ref "R82")
      (value "4.7K")
      (footprint "eagle-import:0805")
      (libsource (lib "eagle-import") (part "RES0805"))
    )
    (comp (ref "SW2")
      (value "BTS50015-1TAD")
      (footprint "eagle-import:TO-263-7-8")
      (libsource (lib "eagle-import") (part "BTS50015-1TAD"))
    )
    (comp (ref "U16")
      (value "LTC4121")
      (footprint "eagle-import:QFN-16-PAD")
      (libsource (lib "eagle-import") (part "LTC4121"))
    )
    (comp (ref "U19")
      (value "AD8418")
      (footprint "eagle-import:MSOP-8")
      (libsource (lib "eagle-import") (part "AD8418"))
    )
    (comp (ref "V44")
      (value "LFB2SNS")
      (footprint "eagle-import:VIA-60MIL")
      (libsource (lib "eagle-import") (part "VIA-60MIL"))
    )
    (comp (ref "V47")
      (value "LFB2_CHG")
      (footprint "eagle-import:VIA-60MIL")
      (libsource (lib "eagle-import") (part "VIA-60MIL"))
    )
    (comp (ref "V49")
      (value "LF3_REF")
      (footprint "eagle-import:VIA-60MIL")
      (libsource (lib "eagle-import") (part "VIA-60MIL"))
    )
    (comp (ref "V50")
      (value "LF4_REF")
      (footprint "eagle-import:VIA-60MIL")
      (libsource (lib "eagle-import") (part "VIA-60MIL"))
    )
    (comp (ref "V51")
      (value "LFB2_OUTEN")
      (footprint "eagle-import:VIA-60MIL")
      (libsource (lib "eagle-import") (part "VIA-60MIL"))
    )
    (comp (ref "V53")
      (value "LF_B2")
      (footprint "eagle-import:VIA-120MIL")
      (libsource (lib "eagle-import") (part "VIA-120MIL"))
    )
    (comp (ref "V99")
      (value "LFB2_OSNS")
      (footprint "eagle-import:VIA-60MIL")
      (libsource (lib "eagle-import") (part "VIA-60MIL"))
    )
  )
  (nets
    (net (code "1") (name "+3V3") (class "Default")
      (node (ref "C1") (pin "1") (pinfunction "P$1_1") (pintype "passive"))
      (node (ref "C2") (pin "1") (pinfunction "P$1_1") (pintype "passive"))
      (node (ref "R17") (pin "2") (pinfunction "2_2") (pintype "passive"))
      (node (ref "R18") (pin "2") (pinfunction "2_2") (pintype "passive"))
      (node (ref "R2") (pin "2") (pinfunction "2_2") (pintype "passive"))
      (node (ref "R20") (pin "1") (pinfunction "1_1") (pintype "passive"))
      (node (ref "R24") (pin "1") (pinfunction "1_1") (pintype "passive"))
      (node (ref "R29") (pin "1") (pinfunction "1_1") (pintype "passive"))
      (node (ref "R3") (pin "2") (pinfunction "2_2") (pintype "passive"))
      (node (ref "R4") (pin "1") (pinfunction "1_1") (pintype "passive"))
      (node (ref "R42") (pin "2") (pinfunction "2_2") (pintype "passive"))
      (node (ref "R43") (pin "2") (pinfunction "2_2") (pintype "passive"))
      (node (ref "R60") (pin "2") (pinfunction "2_2") (pintype "passive"))
      (node (ref "R61") (pin "2") (pinfunction "2_2") (pintype "passive"))
      (node (ref "R83") (pin "2") (pinfunction "2_2") (pintype "passive"))
      (node (ref "R84") (pin "2") (pinfunction "2_2") (pintype "passive"))
      (node (ref "R85") (pin "2") (pinfunction "2_2") (pintype "passive"))
      (node (ref "R86") (pin "2") (pinfunction "2_2") (pintype "passive"))
      (node (ref "U1") (pin "P$24") (pinfunction "VCC_P$24") (pintype "power_in"))
      (node (ref "U18") (pin "P$6") (pinfunction "VS_P$6") (pintype "bidirectional"))
      (node (ref "U19") (pin "P$6") (pinfunction "VS_P$6") (pintype "bidirectional"))
      (node (ref "U2") (pin "P$8") (pinfunction "VDD_P$8") (pintype "bidirectional"))
      (node (ref "U8") (pin "P$6") (pinfunction "VS_P$6") (pintype "bidirectional"))
      (node (ref "U9") (pin "P$6") (pinfunction "VS_P$6") (pintype "bidirectional"))
      (node (ref "V12") (pin "P$1") (pinfunction "P$1_P$1") (pintype "bidirectional"))
    )
    (net (code "2") (name "5V") (class "Default")
      (node (ref "T1") (pin "+") (pinfunction "+_+") (pintype "bidirectional"))
      (node (ref "T2") (pin "+") (pinfunction "+_+") (pintype "bidirectional"))
      (node (ref "T3") (pin "+") (pinfunction "+_+") (pintype "bidirectional"))
      (node (ref "T4") (pin "+") (pinfunction "+_+") (pintype "bidirectional"))
      (node (ref "V7") (pin "P$1") (pinfunction "P$1_P$1") (pintype "bidirectional"))
    )
    (net (code "3") (name "GND") (class "Default")
      (node (ref "C1") (pin "2") (pinfunction "P$2_2") (pintype "passive"))
      (node (ref "C11") (pin "2") (pinfunction "P$2_2") (pintype "passive"))
      (node (ref "C12") (pin "2") (pinfunction "P$2_2") (pintype "passive"))
      (node (ref "C13") (pin "1") (pinfunction "P$1_1") (pintype "passive"))
      (node (ref "C14") (pin "1") (pinfunction "P$1_1") (pintype "passive"))
      (node (ref "C15") (pin "1") (pinfunction "P$1_1") (pintype "passive"))
      (node (ref "C16") (pin "1") (pinfunction "P$1_1") (pintype "passive"))
      (node (ref "C17") (pin "2") (pinfunction "P$2_2") (pintype "passive"))
      (node (ref "C18") (pin "2") (pinfunction "P$2_2") (pintype "passive"))
      (node (ref "C2") (pin "2") (pinfunction "P$2_2") (pintype "passive"))
      (node (ref "C21") (pin "2") (pinfunction "P$2_2") (pintype "passive"))
      (node (ref "C22") (pin "2") (pinfunction "P$2_2") (pintype "passive"))
      (node (ref "C23") (pin "2") (pinfunction "P$2_2") (pintype "passive"))
      (node (ref "C24") (pin "2") (pinfunction "P$2_2") (pintype "passive"))
      (node (ref "C25") (pin "1") (pinfunction "P$1_1") (pintype "passive"))
      (node (ref "C26") (pin "1") (pinfunction "P$1_1") (pintype "passive"))
      (node (ref "C28") (pin "2") (pinfunction "P$2_2") (pintype "passive"))
      (node (ref "C29") (pin "1") (pinfunction "P$1_1") (pintype "passive"))
      (node (ref "C3") (pin "2") (pinfunction "P$2_2") (pintype "passive"))
      (node (ref "C30") (pin "2") (pinfunction "P$2_2") (pintype "passive"))
      (node (ref "C31") (pin "2") (pinfunction "P$2_2") (pintype "passive"))
      (node (ref "C32") (pin "1") (pinfunction "P$1_1") (pintype "passive"))
      (node (ref "C33") (pin "1") (pinfunction "P$1_1") (pintype "passive"))
      (node (ref "C35") (pin "2") (pinfunction "P$2_2") (pintype "passive"))
      (node (ref "C36") (pin "1") (pinfunction "P$1_1") (pintype "passive"))
      (node (ref "C37") (pin "2") (pinfunction "P$2_2") (pintype "passive"))
      (node (ref "C38") (pin "2") (pinfunction "P$2_2") (pintype "passive"))
      (node (ref "C39") (pin "1") (pinfunction "P$1_1") (pintype "passive"))
      (node (ref "C4") (pin "2") (pinfunction "P$2_2") (pintype "passive"))
      (node (ref "C40") (pin "1") (pinfunction "P$1_1") (pintype "passive"))
      (node (ref "C41") (pin "2") (pinfunction "P$2_2") (pintype "passive"))
      (node (ref "C42") (pin "2") (pinfunction "P$2_2") (pintype "passive"))
      (node (ref "C43") (pin "2") (pinfunction "P$2_2") (pintype "passive"))
      (node (ref "C44") (pin "1") (pinfunction "P$1_1") (pintype "passive"))
      (node (ref "C45") (pin "1") (pinfunction "P$1_1") (pintype "passive"))
      (node (ref "C46") (pin "1") (pinfunction "P$1_1") (pintype "passive"))
      (node (ref "C47") (pin "1") (pinfunction "P$1_1") (pintype "passive"))
      (node (ref "C48") (pin "1") (pinfunction "P$1_1") (pintype "passive"))
      (node (ref "C49") (pin "1") (pinfunction "P$1_1") (pintype "passive"))
      (node (ref "C5") (pin "2") (pinfunction "P$2_2") (pintype "passive"))
      (node (ref "C6") (pin "2") (pinfunction "P$2_2") (pintype "passive"))
      (node (ref "C7") (pin "2") (pinfunction "P$2_2") (pintype "passive"))
      (node (ref "C8") (pin "2") (pinfunction "P$2_2") (pintype "passive"))
      (node (ref "D4") (pin "A") (pinfunction "A_A") (pintype "passive"))
      (node (ref "D5") (pin "A") (pinfunction "A_A") (pintype "passive"))
      (node (ref "R11") (pin "1") (pinfunction "1_1") (pintype "passive"))
      (node (ref "R14") (pin "1") (pinfunction "1_1") (pintype "passive"))
      (node (ref "R19") (pin "1") (pinfunction "1_1") (pintype "passive"))
      (node (ref "R21") (pin "2") (pinfunction "2_2") (pintype "passive"))
      (node (ref "R23") (pin "1") (pinfunction "1_1") (pintype "passive"))
      (node (ref "R25") (pin "1") (pinfunction "1_1") (pintype "passive"))
      (node (ref "R26") (pin "2") (pinfunction "2_2") (pintype "passive"))
      (node (ref "R28") (pin "1") (pinfunction "1_1") (pintype "passive"))
      (node (ref "R30") (pin "2") (pinfunction "2_2") (pintype "passive"))
      (node (ref "R32") (pin "1") (pinfunction "1_1") (pintype "passive"))
      (node (ref "R34") (pin "1") (pinfunction "1_1") (pintype "passive"))
      (node (ref "R35") (pin "1") (pinfunction "1_1") (pintype "passive"))
      (node (ref "R36") (pin "1") (pinfunction "1_1") (pintype "passive"))
      (node (ref "R40") (pin "1") (pinfunction "1_1") (pintype "passive"))
      (node (ref "R41") (pin "P$1") (pinfunction "1_P$1") (pintype "passive"))
      (node (ref "R41") (pin "P$2") (pinfunction "1_P$2") (pintype "passive"))
      (node (ref "R44") (pin "1") (pinfunction "1_1") (pintype "passive"))
      (node (ref "R46") (pin "1") (pinfunction "1_1") (pintype "passive"))
      (node (ref "R48") (pin "1") (pinfunction "1_1") (pintype "passive"))
      (node (ref "R5") (pin "1") (pinfunction "1_1") (pintype "passive"))
      (node (ref "R50") (pin "1") (pinfunction "1_1") (pintype "passive"))
      (node (ref "R51") (pin "2") (pinfunction "2_2") (pintype "passive"))
      (node (ref "R54") (pin "1") (pinfunction "1_1") (pintype "passive"))
      (node (ref "R55") (pin "1") (pinfunction "1_1") (pintype "passive"))
      (node (ref "R56") (pin "1") (pinfunction "1_1") (pintype "passive"))
      (node (ref "R57") (pin "1") (pinfunction "1_1") (pintype "passive"))
      (node (ref "R58") (pin "1") (pinfunction "1_1") (pintype "passive"))
      (node (ref "R59") (pin "P$1") (pinfunction "1_P$1") (pintype "passive"))
      (node (ref "R59") (pin "P$2") (pinfunction "1_P$2") (pintype "passive"))
      (node (ref "R6") (pin "2") (pinfunction "2_2") (pintype "passive"))
      (node (ref "R62") (pin "1") (pinfunction "1_1") (pintype "passive"))
      (node (ref "R64") (pin "1") (pinfunction "1_1") (pintype "passive"))
      (node (ref "R66") (pin "1") (pinfunction "1_1") (pintype "passive"))
      (node (ref "R68") (pin "1") (pinfunction "1_1") (pintype "passive"))
      (node (ref "R69") (pin "2") (pinfunction "2_2") (pintype "passive"))
      (node (ref "R72") (pin "1") (pinfunction "1_1") (pintype "passive"))
      (node (ref "R76") (pin "1") (pinfunction "1_1") (pintype "passive"))
      (node (ref "R77") (pin "1") (pinfunction "1_1") (pintype "passive"))
      (node (ref "R8") (pin "1") (pinfunction "1_1") (pintype "passive"))
      (node (ref "R80") (pin "1") (pinfunction "1_1") (pintype "passive"))
      (node (ref "R9") (pin "1") (pinfunction "1_1") (pintype "passive"))
      (node (ref "SW1") (pin "P$1") (pinfunction "GND_P$1") (pintype "bidirectional"))
      (node (ref "SW2") (pin "P$1") (pinfunction "GND_P$1") (pintype "bidirectional"))
      (node (ref "U1") (pin "P$12") (pinfunction "GND_P$12") (pintype "power_in"))
      (node (ref "U1") (pin "P$2") (pinfunction "A1_P$2") (pintype "bidirectional"))
      (node (ref "U1") (pin "P$21") (pinfunction "A0_P$21") (pintype "bidirectional"))
      (node (ref "U1") (pin "P$3") (pinfunction "A2_P$3") (pintype "bidirectional"))
      (node (ref "U10") (pin "P$4") (pinfunction "GND_P$4") (pintype "bidirectional"))
      (node (ref "U10") (pin "P$6") (pinfunction "NC_P$6") (pintype "bidirectional"))
      (node (ref "U10") (pin "P$7") (pinfunction "NC_P$7") (pintype "bidirectional"))
      (node (ref "U11") (pin "P$4") (pinfunction "GND_P$4") (pintype "bidirectional"))
      (node (ref "U11") (pin "P$6") (pinfunction "NC_P$6") (pintype "bidirectional"))
      (node (ref "U11") (pin "P$7") (pinfunction "NC_P$7") (pintype "bidirectional"))
      (node (ref "U12") (pin "P$2") (pinfunction "GND_P$2") (pintype "bidirectional"))
      (node (ref "U13") (pin "P$2") (pinfunction "GND_P$2") (pintype "bidirectional"))
      (node (ref "U14") (pin "P$12") (pinfunction "NTC_P$12") (pintype "bidirectional"))
      (node (ref "U14") (pin "P$17") (pinfunction "GND_P$17") (pintype "bidirectional"))
      (node (ref "U14") (pin "P$5") (pinfunction "GND_P$5") (pintype "bidirectional"))
      (node (ref "U14") (pin "P$7") (pinfunction "FREQ_P$7") (pintype "bidirectional"))
      (node (ref "U16") (pin "P$12") (pinfunction "NTC_P$12") (pintype "bidirectional"))
      (node (ref "U16") (pin "P$17") (pinfunction "GND_P$17") (pintype "bidirectional"))
      (node (ref "U16") (pin "P$5") (pinfunction "GND_P$5") (pintype "bidirectional"))
      (node (ref "U16") (pin "P$7") (pinfunction "FREQ_P$7") (pintype "bidirectional"))
      (node (ref "U18") (pin "P$1") (pinfunction "-IN_P$1") (pintype "bidirectional"))
      (node (ref "U18") (pin "P$2") (pinfunction "GND_P$2") (pintype "bidirectional"))
      (node (ref "U18") (pin "P$4") (pinfunction "NC_P$4") (pintype "bidirectional"))
      (node (ref "U19") (pin "P$1") (pinfunction "-IN_P$1") (pintype "bidirectional"))
      (node (ref "U19") (pin "P$2") (pinfunction "GND_P$2") (pintype "bidirectional"))
      (node (ref "U19") (pin "P$4") (pinfunction "NC_P$4") (pintype "bidirectional"))
      (node (ref "U2") (pin "P$7") (pinfunction "GND_P$7") (pintype "bidirectional"))
      (node (ref "U3") (pin "P$2") (pinfunction "GND_P$2") (pintype "bidirectional"))
      (node (ref "U3") (pin "P$3") (pinfunction "CNTL_P$3") (pintype "bidirectional"))
      (node (ref "U4") (pin "P$11") (pinfunction "NC_P$11") (pintype "bidirectional"))
      (node (ref "U4") (pin "P$12") (pinfunction "NTC_P$12") (pintype "bidirectional"))
      (node (ref "U4") (pin "P$17") (pinfunction "GND_P$17") (pintype "bidirectional"))
      (node (ref "U4") (pin "P$5") (pinfunction "GND_P$5") (pintype "bidirectional"))
      (node (ref "U4") (pin "P$7") (pinfunction "FREQ_P$7") (pintype "bidirectional"))
      (node (ref "U5") (pin "P$11") (pinfunction "NC_P$11") (pintype "bidirectional"))
      (node (ref "U5") (pin "P$12") (pinfunction "NTC_P$12") (pintype "bidirectional"))
      (node (ref "U5") (pin "P$17") (pinfunction "GND_P$17") (pintype "bidirectional"))
      (node (ref "U5") (pin "P$5") (pinfunction "GND_P$5") (pintype "bidirectional"))
      (node (ref "U5") (pin "P$7") (pinfunction "FREQ_P$7") (pintype "bidirectional"))
      (node (ref "U6") (pin "P$1") (pinfunction "S2_P$1") (pintype "bidirectional"))
      (node (ref "U6") (pin "P$3") (pinfunction "TST_P$3") (pintype "bidirectional"))
      (node (ref "U6") (pin "P$4") (pinfunction "VSS_P$4") (pintype "bidirectional"))
      (node (ref "U7") (pin "P$1") (pinfunction "S2_P$1") (pintype "bidirectional"))
      (node (ref "U7") (pin "P$3") (pinfunction "TST_P$3") (pintype "bidirectional"))
      (node (ref "U7") (pin "P$4") (pinfunction "VSS_P$4") (pintype "bidirectional"))
      (node (ref "U8") (pin "P$2") (pinfunction "GND_P$2") (pintype "bidirectional"))
      (node (ref "U8") (pin "P$4") (pinfunction "NC_P$4") (pintype "bidirectional"))
      (node (ref "U9") (pin "P$2") (pinfunction "GND_P$2") (pintype "bidirectional"))
      (node (ref "U9") (pin "P$4") (pinfunction "NC_P$4") (pintype "bidirectional"))
      (node (ref "V1") (pin "P$1") (pinfunction "P$1_P$1") (pintype "bidirectional"))
      (node (ref "V2") (pin "P$1") (pinfunction "P$1_P$1") (pintype "bidirectional"))
      (node (ref "V28") (pin "P$1") (pinfunction "P$1_P$1") (pintype "bidirectional"))
      (node (ref "V3") (pin "P$1") (pinfunction "P$1_P$1") (pintype "bidirectional"))
      (node (ref "V36") (pin "P$1") (pinfunction "P$1_P$1") (pintype "bidirectional"))
      (node (ref "V4") (pin "P$1") (pinfunction "P$1_P$1") (pintype "bidirectional"))
    )
    (net (code "4") (name "L1_CHG") (class "Default")
      (node (ref "R15") (pin "2") (pinfunction "2_2") (pintype "passive"))
      (node (ref "R35") (pin "2") (pinfunction "2_2") (pintype "passive"))
      (node (ref "U4") (pin "P$16") (pinfunction "RUN_P$16") (pintype "bidirectional"))
      (node (ref "V20") (pin "P$1") (pinfunction "P$1_P$1") (pintype "bidirectional"))
      (node (ref "V48") (pin "P$1") (pinfunction "P$1_P$1") (pintype "bidirectional"))
    )
    (net (code "5") (name "L1_CHGN") (class "Default")
      (node (ref "R17") (pin "1") (pinfunction "1_1") (pintype "passive"))
      (node (ref "U1") (pin "P$8") (pinfunction "P04_P$8") (pintype "bidirectional"))
      (node (ref "U4") (pin "P$14") (pinfunction "~{CHRG}_P$14") (pintype "bidirectional"))
      (node (ref "V27") (pin "P$1") (pinfunction "P$1_P$1") (pintype "bidirectional"))
    )
    (net (code "6") (name "L1_DISG") (class "Default")
      (node (ref "R5") (pin "2") (pinfunction "2_2") (pintype "passive"))
      (node (ref "U12") (pin "P$3") (pinfunction "CNTRL_P$3") (pintype "bidirectional"))
      (node (ref "V29") (pin "P$1") (pinfunction "P$1_P$1") (pintype "bidirectional"))
    )
    (net (code "7") (name "L1_FAULTN") (class "Default")
      (node (ref "R18") (pin "1") (pinfunction "1_1") (pintype "passive"))
      (node (ref "U1") (pin "P$9") (pinfunction "P05_P$9") (pintype "bidirectional"))
      (node (ref "U4") (pin "P$15") (pinfunction "~{FAULT}_P$15") (pintype "bidirectional"))
      (node (ref "V26") (pin "P$1") (pinfunction "P$1_P$1") (pintype "bidirectional"))
    )
    (net (code "8") (name "L1_PROG") (class "Default")
      (node (ref "R25") (pin "2") (pinfunction "2_2") (pintype "passive"))
      (node (ref "U4") (pin "P$13") (pinfunction "PROG_P$13") (pintype "bidirectional"))
    )
    (net (code "9") (name "L1_REF") (class "Default")
      (node (ref "R33") (pin "1") (pinfunction "1_1") (pintype "passive"))
      (node (ref "R34") (pin "2") (pinfunction "2_2") (pintype "passive"))
      (node (ref "V21") (pin "P$1") (pinfunction "P$1_P$1") (pintype "bidirectional"))
    )
    (net (code "10") (name "L1_SNS") (class "Default")
      (node (ref "C39") (pin "2") (pinfunction "P$2_2") (pintype "passive"))
      (node (ref "U2") (pin "P$4") (pinfunction "VIN1_P$4") (pintype "bidirectional"))
      (node (ref "U8") (pin "P$5") (pinfunction "OUT_P$5") (pintype "bidirectional"))
    )
    (net (code "11") (name "L1_SNS+") (class "Default")
      (node (ref "LI-ION1") (pin "MINUS") (pinfunction "MINUS_MINUS") (pintype "power_in"))
      (node (ref "R31") (pin "P$2") (pinfunction "2_P$2") (pintype "passive"))
      (node (ref "U8") (pin "P$8") (pinfunction "+IN_P$8") (pintype "bidirectional"))
    )
    (net (code "12") (name "L1_SNS-") (class "Default")
      (node (ref "R31") (pin "P$1") (pinfunction "1_P$1") (pintype "passive"))
      (node (ref "U8") (pin "P$1") (pinfunction "-IN_P$1") (pintype "bidirectional"))
      (node (ref "V22") (pin "P$1") (pinfunction "P$1_P$1") (pintype "bidirectional"))
    )
    (net (code "13") (name "L1_ST") (class "Default")
      (node (ref "R37") (pin "1") (pinfunction "1_1") (pintype "passive"))
      (node (ref "U1") (pin "P$5") (pinfunction "P01_P$5") (pintype "bidirectional"))
      (node (ref "U12") (pin "P$4") (pinfunction "STAT_P$4") (pintype "bidirectional"))
    )
    (net (code "14") (name "L1_TEMP") (class "Default")
      (node (ref "T1") (pin "-") (pinfunction "-_-") (pintype "bidirectional"))
      (node (ref "V8") (pin "P$1") (pinfunction "P$1_P$1") (pintype "bidirectional"))
    )
    (net (code "15") (name "L2_CHG") (class "Default")
      (node (ref "R1") (pin "2") (pinfunction "2_2") (pintype "passive"))
      (node (ref "R36") (pin "2") (pinfunction "2_2") (pintype "passive"))
      (node (ref "U5") (pin "P$16") (pinfunction "RUN_P$16") (pintype "bidirectional"))
      (node (ref "V33") (pin "P$1") (pinfunction "P$1_P$1") (pintype "bidirectional"))
    )
    (net (code "16") (name "L2_CHGN") (class "Default")
      (node (ref "R2") (pin "1") (pinfunction "1_1") (pintype "passive"))
      (node (ref "U1") (pin "P$10") (pinfunction "P06_P$10") (pintype "bidirectional"))
      (node (ref "U5") (pin "P$14") (pinfunction "~{CHRG}_P$14") (pintype "bidirectional"))
    )
    (net (code "17") (name "L2_DISG") (class "Default")
      (node (ref "R54") (pin "2") (pinfunction "2_2") (pintype "passive"))
      (node (ref "U13") (pin "P$3") (pinfunction "CNTRL_P$3") (pintype "bidirectional"))
      (node (ref "V30") (pin "P$1") (pinfunction "P$1_P$1") (pintype "bidirectional"))
    )
    (net (code "18") (name "L2_FAULTN") (class "Default")
      (node (ref "R3") (pin "1") (pinfunction "1_1") (pintype "passive"))
      (node (ref "U1") (pin "P$11") (pinfunction "P07_P$11") (pintype "bidirectional"))
      (node (ref "U5") (pin "P$15") (pinfunction "~{FAULT}_P$15") (pintype "bidirectional"))
    )
    (net (code "19") (name "L2_PROG") (class "Default")
      (node (ref "R9") (pin "2") (pinfunction "2_2") (pintype "passive"))
      (node (ref "U5") (pin "P$13") (pinfunction "PROG_P$13") (pintype "bidirectional"))
    )
    (net (code "20") (name "L2_REF") (class "Default")
      (node (ref "C41") (pin "1") (pinfunction "P$1_1") (pintype "passive"))
      (node (ref "R16") (pin "1") (pinfunction "1_1") (pintype "passive"))
      (node (ref "R19") (pin "2") (pinfunction "2_2") (pintype "passive"))
      (node (ref "V31") (pin "P$1") (pinfunction "P$1_P$1") (pintype "bidirectional"))
    )
    (net (code "21") (name "L2_SNS") (class "Default")
      (node (ref "C40") (pin "2") (pinfunction "P$2_2") (pintype "passive"))
      (node (ref "U2") (pin "P$3") (pinfunction "VIN0_P$3") (pintype "bidirectional"))
      (node (ref "U9") (pin "P$5") (pinfunction "OUT_P$5") (pintype "bidirectional"))
    )
    (net (code "22") (name "L2_SNS+") (class "Default")
      (node (ref "LI-ION2") (pin "MINUS") (pinfunction "MINUS_MINUS") (pintype "power_in"))
      (node (ref "R12") (pin "P$2") (pinfunction "2_P$2") (pintype "passive"))
      (node (ref "U9") (pin "P$8") (pinfunction "+IN_P$8") (pintype "bidirectional"))
    )
    (net (code "23") (name "L2_SNS-") (class "Default")
      (node (ref "R12") (pin "P$1") (pinfunction "1_P$1") (pintype "passive"))
      (node (ref "U9") (pin "P$1") (pinfunction "-IN_P$1") (pintype "bidirectional"))
      (node (ref "V24") (pin "P$1") (pinfunction "P$1_P$1") (pintype "bidirectional"))
    )
    (net (code "24") (name "L2_ST") (class "Default")
      (node (ref "R38") (pin "1") (pinfunction "1_1") (pintype "passive"))
      (node (ref "U1") (pin "P$4") (pinfunction "P00_P$4") (pintype "bidirectional"))
      (node (ref "U13") (pin "P$4") (pinfunction "STAT_P$4") (pintype "bidirectional"))
    )
    (net (code "25") (name "L2_TEMP") (class "Default")
      (node (ref "T2") (pin "-") (pinfunction "-_-") (pintype "bidirectional"))
      (node (ref "V9") (pin "P$1") (pinfunction "P$1_P$1") (pintype "bidirectional"))
    )
    (net (code "26") (name "LF-B1-CHG-IN") (class "Default")
      (node (ref "C25") (pin "2") (pinfunction "P$2_2") (pintype "passive"))
      (node (ref "D8") (pin "C") (pinfunction "C_C") (pintype "bidirectional"))
      (node (ref "R45") (pin "2") (pinfunction "2_2") (pintype "passive"))
      (node (ref "U14") (pin "P$3") (pinfunction "IN_P$3") (pintype "bidirectional"))
    )
    (net (code "27") (name "LF-B2-CHG-IN") (class "Default")
      (node (ref "C32") (pin "2") (pinfunction "P$2_2") (pintype "passive"))
      (node (ref "D9") (pin "C") (pinfunction "C_C") (pintype "bidirectional"))
      (node (ref "R63") (pin "2") (pinfunction "2_2") (pintype "passive"))
      (node (ref "U16") (pin "P$3") (pinfunction "IN_P$3") (pintype "bidirectional"))
    )
    (net (code "28") (name "LF1_REF") (class "Default")
      (node (ref "C46") (pin "2") (pinfunction "P$2_2") (pintype "passive"))
      (node (ref "R49") (pin "2") (pinfunction "2_2") (pintype "passive"))
      (node (ref "R50") (pin "2") (pinfunction "2_2") (pintype "passive"))
      (node (ref "V41") (pin "P$1") (pinfunction "P$1_P$1") (pintype "bidirectional"))
    )
    (net (code "29") (name "LF1_TEMP") (class "Default")
      (node (ref "T3") (pin "-") (pinfunction "-_-") (pintype "bidirectional"))
      (node (ref "V10") (pin "P$1") (pinfunction "P$1_P$1") (pintype "bidirectional"))
    )
    (net (code "30") (name "LF2_REF") (class "Default")
      (node (ref "C45") (pin "2") (pinfunction "P$2_2") (pintype "passive"))
      (node (ref "R47") (pin "1") (pinfunction "1_1") (pintype "passive"))
      (node (ref "R48") (pin "2") (pinfunction "2_2") (pintype "passive"))
      (node (ref "V42") (pin "P$1") (pinfunction "P$1_P$1") (pintype "bidirectional"))
    )
    (net (code "31") (name "LF3_REF") (class "Default")
      (node (ref "C47") (pin "2") (pinfunction "P$2_2") (pintype "passive"))
      (node (ref "R67") (pin "2") (pinfunction "2_2") (pintype "passive"))
      (node (ref "R68") (pin "2") (pinfunction "2_2") (pintype "passive"))
      (node (ref "V49") (pin "P$1") (pinfunction "P$1_P$1") (pintype "bidirectional"))
    )
    (net (code "32") (name "LF3_TEMP") (class "Default")
      (node (ref "T4") (pin "-") (pinfunction "-_-") (pintype "bidirectional"))
      (node (ref "V11") (pin "P$1") (pinfunction "P$1_P$1") (pintype "bidirectional"))
    )
    (net (code "33") (name "LF4_REF") (class "Default")
      (node (ref "C48") (pin "2") (pinfunction "P$2_2") (pintype "passive"))
      (node (ref "R65") (pin "1") (pinfunction "1_1") (pintype "passive"))
      (node (ref "R66") (pin "2") (pinfunction "2_2") (pintype "passive"))
      (node (ref "V50") (pin "P$1") (pinfunction "P$1_P$1") (pintype "bidirectional"))
    )
    (net (code "34") (name "LFB1_SNS+") (class "Default")
      (node (ref "LIFEPO42") (pin "MINUS") (pinfunction "MINUS_MINUS") (pintype "power_in"))
      (node (ref "R41") (pin "P$3") (pinfunction "2_P$3") (pintype "passive"))
      (node (ref "R41") (pin "P$4") (pinfunction "2_P$4") (pintype "passive"))
      (node (ref "U18") (pin "P$8") (pinfunction "+IN_P$8") (pintype "bidirectional"))
    )
    (net (code "35") (name "LFB2_SNS+") (class "Default")
      (node (ref "LIFEPO44") (pin "MINUS") (pinfunction "MINUS_MINUS") (pintype "power_in"))
      (node (ref "R59") (pin "P$3") (pinfunction "2_P$3") (pintype "passive"))
      (node (ref "R59") (pin "P$4") (pinfunction "2_P$4") (pintype "passive"))
      (node (ref "U19") (pin "P$8") (pinfunction "+IN_P$8") (pintype "bidirectional"))
    )
    (net (code "36") (name "LF_B1") (class "Default")
      (node (ref "C30") (pin "1") (pinfunction "P$1_1") (pintype "passive"))
      (node (ref "SW1") (pin "P$5") (pinfunction "OUT_P$5") (pintype "power_in"))
      (node (ref "SW1") (pin "P$6") (pinfunction "OUT_P$6") (pintype "power_in"))
      (node (ref "SW1") (pin "P$7") (pinfunction "OUT_P$7") (pintype "power_in"))
      (node (ref "V45") (pin "P$1") (pinfunction "P$1_P$1") (pintype "bidirectional"))
    )
    (net (code "38") (name "LF_B1_CHG") (class "Default")
      (node (ref "R44") (pin "2") (pinfunction "2_2") (pintype "passive"))
      (node (ref "U14") (pin "P$16") (pinfunction "RUN_P$16") (pintype "bidirectional"))
      (node (ref "V32") (pin "P$1") (pinfunction "P$1_P$1") (pintype "bidirectional"))
      (node (ref "V35") (pin "P$1") (pinfunction "P$1_P$1") (pintype "bidirectional"))
    )
    (net (code "39") (name "LF_B1_CHGN") (class "Default")
      (node (ref "R42") (pin "1") (pinfunction "1_1") (pintype "passive"))
      (node (ref "U1") (pin "P$20") (pinfunction "P17_P$20") (pintype "bidirectional"))
      (node (ref "U14") (pin "P$14") (pinfunction "~{CHRG}_P$14") (pintype "bidirectional"))
    )
    (net (code "40") (name "LF_B1_FAULTN") (class "Default")
      (node (ref "R43") (pin "1") (pinfunction "1_1") (pintype "passive"))
      (node (ref "U1") (pin "P$19") (pinfunction "P16_P$19") (pintype "bidirectional"))
      (node (ref "U14") (pin "P$15") (pinfunction "~{FAULT}_P$15") (pintype "bidirectional"))
    )
    (net (code "41") (name "LF_B1_OSNS") (class "Default")
      (node (ref "C31") (pin "1") (pinfunction "P$1_1") (pintype "passive"))
      (node (ref "R79") (pin "1") (pinfunction "1_1") (pintype "passive"))
      (node (ref "V46") (pin "P$1") (pinfunction "P$1_P$1") (pintype "bidirectional"))
    )
    (net (code "42") (name "LF_B1_OUTEN") (class "Default")
      (node (ref "R78") (pin "1") (pinfunction "1_1") (pintype "passive"))
      (node (ref "V43") (pin "P$1") (pinfunction "P$1_P$1") (pintype "bidirectional"))
    )
    (net (code "43") (name "LF_B1_SNS") (class "Default")
      (node (ref "C44") (pin "2") (pinfunction "P$2_2") (pintype "passive"))
      (node (ref "U18") (pin "P$5") (pinfunction "OUT_P$5") (pintype "bidirectional"))
      (node (ref "V40") (pin "P$1") (pinfunction "P$1_P$1") (pintype "bidirectional"))
    )
    (net (code "45") (name "LF_B2") (class "Default")
      (node (ref "C37") (pin "1") (pinfunction "P$1_1") (pintype "passive"))
      (node (ref "SW2") (pin "P$5") (pinfunction "OUT_P$5") (pintype "power_in"))
      (node (ref "SW2") (pin "P$6") (pinfunction "OUT_P$6") (pintype "power_in"))
      (node (ref "SW2") (pin "P$7") (pinfunction "OUT_P$7") (pintype "power_in"))
      (node (ref "V53") (pin "P$1") (pinfunction "P$1_P$1") (pintype "bidirectional"))
    )
    (net (code "47") (name "LF_B2_CHG") (class "Default")
      (node (ref "R62") (pin "2") (pinfunction "2_2") (pintype "passive"))
      (node (ref "U16") (pin "P$16") (pinfunction "RUN_P$16") (pintype "bidirectional"))
      (node (ref "V47") (pin "P$1") (pinfunction "P$1_P$1") (pintype "bidirectional"))
    )
    (net (code "48") (name "LF_B2_CHGN") (class "Default")
      (node (ref "R60") (pin "1") (pinfunction "1_1") (pintype "passive"))
      (node (ref "U1") (pin "P$17") (pinfunction "P14_P$17") (pintype "bidirectional"))
      (node (ref "U16") (pin "P$14") (pinfunction "~{CHRG}_P$14") (pintype "bidirectional"))
    )
    (net (code "49") (name "LF_B2_FAULTN") (class "Default")
      (node (ref "R61") (pin "1") (pinfunction "1_1") (pintype "passive"))
      (node (ref "U1") (pin "P$18") (pinfunction "P15_P$18") (pintype "bidirectional"))
      (node (ref "U16") (pin "P$15") (pinfunction "~{FAULT}_P$15") (pintype "bidirectional"))
    )
    (net (code "50") (name "LF_B2_OSNS") (class "Default")
      (node (ref "C38") (pin "1") (pinfunction "P$1_1") (pintype "passive"))
      (node (ref "R82") (pin "1") (pinfunction "1_1") (pintype "passive"))
      (node (ref "V99") (pin "P$1") (pinfunction "P$1_P$1") (pintype "bidirectional"))
    )
    (net (code "51") (name "LF_B2_OUTEN") (class "Default")
      (node (ref "R81") (pin "1") (pinfunction "1_1") (pintype "passive"))
      (node (ref "V51") (pin "P$1") (pinfunction "P$1_P$1") (pintype "bidirectional"))
    )
    (net (code "52") (name "LF_B2_SNS") (class "Default")
      (node (ref "C49") (pin "2") (pinfunction "P$2_2") (pintype "passive"))
      (node (ref "U19") (pin "P$5") (pinfunction "OUT_P$5") (pintype "bidirectional"))
      (node (ref "V44") (pin "P$1") (pinfunction "P$1_P$1") (pintype "bidirectional"))
    )
    (net (code "54") (name "LIFE1") (class "Default")
      (node (ref "C28") (pin "1") (pinfunction "P$1_1") (pintype "passive"))
      (node (ref "D4") (pin "C") (pinfunction "C_C") (pintype "passive"))
      (node (ref "F3") (pin "P$1") (pinfunction "P$1_P$1") (pintype "passive"))
      (node (ref "F4") (pin "P$1") (pinfunction "P$1_P$1") (pintype "passive"))
      (node (ref "LIFEPO41") (pin "PLUS") (pinfunction "PLUS_PLUS") (pintype "power_in"))
      (node (ref "R49") (pin "1") (pinfunction "1_1") (pintype "passive"))
      (node (ref "R53") (pin "2") (pinfunction "2_2") (pintype "passive"))
      (node (ref "U14") (pin "P$9") (pinfunction "BAT_P$9") (pintype "bidirectional"))
    )
    (net (code "55") (name "LIFE1FUSEOUT") (class "Default")
      (node (ref "F3") (pin "P$2") (pinfunction "P$2_P$2") (pintype "passive"))
      (node (ref "F4") (pin "P$2") (pinfunction "P$2_P$2") (pintype "passive"))
      (node (ref "SW1") (pin "PAD") (pinfunction "VB_PAD") (pintype "power_in"))
    )
    (net (code "56") (name "LIFE3") (class "Default")
      (node (ref "C35") (pin "1") (pinfunction "P$1_1") (pintype "passive"))
      (node (ref "D5") (pin "C") (pinfunction "C_C") (pintype "passive"))
      (node (ref "F5") (pin "P$1") (pinfunction "P$1_P$1") (pintype "passive"))
      (node (ref "F6") (pin "P$1") (pinfunction "P$1_P$1") (pintype "passive"))
      (node (ref "LIFEPO43") (pin "PLUS") (pinfunction "PLUS_PLUS") (pintype "power_in"))
      (node (ref "R67") (pin "1") (pinfunction "1_1") (pintype "passive"))
      (node (ref "R71") (pin "2") (pinfunction "2_2") (pintype "passive"))
      (node (ref "U16") (pin "P$9") (pinfunction "BAT_P$9") (pintype "bidirectional"))
    )
    (net (code "57") (name "LIFE3FUSEOUT") (class "Default")
      (node (ref "F5") (pin "P$2") (pinfunction "P$2_P$2") (pintype "passive"))
      (node (ref "F6") (pin "P$2") (pinfunction "P$2_P$2") (pintype "passive"))
      (node (ref "SW2") (pin "PAD") (pinfunction "VB_PAD") (pintype "power_in"))
    )
    (net (code "58") (name "LION1") (class "Default")
      (node (ref "C11") (pin "1") (pinfunction "P$1_1") (pintype "passive"))
      (node (ref "F1") (pin "1") (pinfunction "P$1_1") (pintype "passive"))
      (node (ref "LI-ION1") (pin "PLUS") (pinfunction "PLUS_PLUS") (pintype "power_in"))
      (node (ref "R33") (pin "2") (pinfunction "2_2") (pintype "passive"))
      (node (ref "R7") (pin "2") (pinfunction "2_2") (pintype "passive"))
      (node (ref "U4") (pin "P$10") (pinfunction "BATSNS_P$10") (pintype "bidirectional"))
      (node (ref "U4") (pin "P$9") (pinfunction "BAT_P$9") (pintype "bidirectional"))
    )
    (net (code "59") (name "LION1-CHG-IN") (class "Default")
      (node (ref "C5") (pin "1") (pinfunction "P$1_1") (pintype "passive"))
      (node (ref "D6") (pin "C") (pinfunction "C_C") (pintype "bidirectional"))
      (node (ref "R15") (pin "1") (pinfunction "1_1") (pintype "passive"))
      (node (ref "R27") (pin "2") (pinfunction "2_2") (pintype "passive"))
      (node (ref "U4") (pin "P$3") (pinfunction "IN_P$3") (pintype "bidirectional"))
    )
    (net (code "60") (name "LION1_OUT") (class "Default")
      (node (ref "C15") (pin "2") (pinfunction "P$2_2") (pintype "passive"))
      (node (ref "F1") (pin "2") (pinfunction "P$2_2") (pintype "passive"))
      (node (ref "U12") (pin "P$1") (pinfunction "IN_P$1") (pintype "bidirectional"))
    )
    (net (code "61") (name "LION2") (class "Default")
      (node (ref "C12") (pin "1") (pinfunction "P$1_1") (pintype "passive"))
      (node (ref "F2") (pin "1") (pinfunction "P$1_1") (pintype "passive"))
      (node (ref "LI-ION2") (pin "PLUS") (pinfunction "PLUS_PLUS") (pintype "power_in"))
      (node (ref "R16") (pin "2") (pinfunction "2_2") (pintype "passive"))
      (node (ref "R22") (pin "2") (pinfunction "2_2") (pintype "passive"))
      (node (ref "U5") (pin "P$10") (pinfunction "BATSNS_P$10") (pintype "bidirectional"))
      (node (ref "U5") (pin "P$9") (pinfunction "BAT_P$9") (pintype "bidirectional"))
    )
    (net (code "62") (name "LION2_OUT") (class "Default")
      (node (ref "C16") (pin "2") (pinfunction "P$2_2") (pintype "passive"))
      (node (ref "F2") (pin "2") (pinfunction "P$2_2") (pintype "passive"))
      (node (ref "U13") (pin "P$1") (pinfunction "IN_P$1") (pintype "bidirectional"))
    )
    (net (code "63") (name "L_OUT") (class "Default")
      (node (ref "C21") (pin "1") (pinfunction "P$1_1") (pintype "passive"))
      (node (ref "C22") (pin "1") (pinfunction "P$1_1") (pintype "passive"))
      (node (ref "D2") (pin "C") (pinfunction "C_C") (pintype "bidirectional"))
      (node (ref "D3") (pin "C") (pinfunction "C_C") (pintype "bidirectional"))
      (node (ref "R37") (pin "2") (pinfunction "2_2") (pintype "passive"))
      (node (ref "R38") (pin "2") (pinfunction "2_2") (pintype "passive"))
      (node (ref "R39") (pin "2") (pinfunction "2_2") (pintype "passive"))
      (node (ref "U12") (pin "P$5") (pinfunction "OUT_P$5") (pintype "bidirectional"))
      (node (ref "U13") (pin "P$5") (pinfunction "OUT_P$5") (pintype "bidirectional"))
      (node (ref "V34") (pin "P$1") (pinfunction "P$1_P$1") (pintype "bidirectional"))
    )
    (net (code "64") (name "L_REF") (class "Default")
      (node (ref "C42") (pin "1") (pinfunction "P$1_1") (pintype "passive"))
      (node (ref "R39") (pin "1") (pinfunction "1_1") (pintype "passive"))
      (node (ref "R40") (pin "2") (pinfunction "2_2") (pintype "passive"))
      (node (ref "U2") (pin "P$5") (pinfunction "VIN2_P$5") (pintype "bidirectional"))
    )
    (net (code "65") (name "Net-(C6-P$1)") (class "Default")
      (node (ref "C6") (pin "1") (pinfunction "P$1_1") (pintype "passive"))
      (node (ref "D7") (pin "C") (pinfunction "C_C") (pintype "bidirectional"))
      (node (ref "R1") (pin "1") (pinfunction "1_1") (pintype "passive"))
      (node (ref "R10") (pin "2") (pinfunction "2_2") (pintype "passive"))
      (node (ref "U5") (pin "P$3") (pinfunction "IN_P$3") (pintype "bidirectional"))
    )
    (net (code "66") (name "Net-(C7-P$1)") (class "Default")
      (node (ref "C7") (pin "1") (pinfunction "P$1_1") (pintype "passive"))
      (node (ref "U4") (pin "P$1") (pinfunction "INTVCC_P$1") (pintype "bidirectional"))
    )
    (net (code "67") (name "Net-(C8-P$1)") (class "Default")
      (node (ref "C8") (pin "1") (pinfunction "P$1_1") (pintype "passive"))
      (node (ref "U5") (pin "P$1") (pinfunction "INTVCC_P$1") (pintype "bidirectional"))
    )
    (net (code "68") (name "Net-(C9-P$1)") (class "Default")
      (node (ref "C9") (pin "1") (pinfunction "P$1_1") (pintype "passive"))
      (node (ref "U4") (pin "P$2") (pinfunction "BOOST_P$2") (pintype "bidirectional"))
    )
    (net (code "69") (name "Net-(C9-P$2)") (class "Default")
      (node (ref "C9") (pin "2") (pinfunction "P$2_2") (pintype "passive"))
      (node (ref "L1") (pin "P$1") (pinfunction "P$1_P$1") (pintype "passive"))
      (node (ref "U4") (pin "P$4") (pinfunction "SW_P$4") (pintype "bidirectional"))
    )
    (net (code "70") (name "Net-(C10-P$1)") (class "Default")
      (node (ref "C10") (pin "1") (pinfunction "P$1_1") (pintype "passive"))
      (node (ref "U5") (pin "P$2") (pinfunction "BOOST_P$2") (pintype "bidirectional"))
    )
    (net (code "71") (name "Net-(C10-P$2)") (class "Default")
      (node (ref "C10") (pin "2") (pinfunction "P$2_2") (pintype "passive"))
      (node (ref "L2") (pin "P$1") (pinfunction "P$1_P$1") (pintype "passive"))
      (node (ref "U5") (pin "P$4") (pinfunction "SW_P$4") (pintype "bidirectional"))
    )
    (net (code "72") (name "Net-(C13-P$2)") (class "Default")
      (node (ref "C13") (pin "2") (pinfunction "P$2_2") (pintype "passive"))
      (node (ref "R7") (pin "1") (pinfunction "1_1") (pintype "passive"))
      (node (ref "U6") (pin "P$5") (pinfunction "VCC_P$5") (pintype "bidirectional"))
    )
    (net (code "73") (name "Net-(C14-P$2)") (class "Default")
      (node (ref "C14") (pin "2") (pinfunction "P$2_2") (pintype "passive"))
      (node (ref "R22") (pin "1") (pinfunction "1_1") (pintype "passive"))
      (node (ref "U7") (pin "P$5") (pinfunction "VCC_P$5") (pintype "bidirectional"))
    )
    (net (code "74") (name "Net-(C19-P$1)") (class "Default")
      (node (ref "C19") (pin "1") (pinfunction "P$1_1") (pintype "passive"))
      (node (ref "C23") (pin "1") (pinfunction "P$1_1") (pintype "passive"))
      (node (ref "D2") (pin "A") (pinfunction "A_A") (pintype "bidirectional"))
      (node (ref "U10") (pin "P$1") (pinfunction "OUT_P$1") (pintype "bidirectional"))
      (node (ref "U10") (pin "P$2") (pinfunction "SENSE_P$2") (pintype "bidirectional"))
    )
    (net (code "75") (name "Net-(C19-P$2)") (class "Default")
      (node (ref "C19") (pin "2") (pinfunction "P$2_2") (pintype "passive"))
      (node (ref "U10") (pin "P$3") (pinfunction "BYP_P$3") (pintype "bidirectional"))
    )
    (net (code "76") (name "Net-(C20-P$1)") (class "Default")
      (node (ref "C20") (pin "1") (pinfunction "P$1_1") (pintype "passive"))
      (node (ref "C24") (pin "1") (pinfunction "P$1_1") (pintype "passive"))
      (node (ref "D3") (pin "A") (pinfunction "A_A") (pintype "bidirectional"))
      (node (ref "U11") (pin "P$1") (pinfunction "OUT_P$1") (pintype "bidirectional"))
      (node (ref "U11") (pin "P$2") (pinfunction "SENSE_P$2") (pintype "bidirectional"))
    )
    (net (code "77") (name "Net-(C20-P$2)") (class "Default")
      (node (ref "C20") (pin "2") (pinfunction "P$2_2") (pintype "passive"))
      (node (ref "U11") (pin "P$3") (pinfunction "BYP_P$3") (pintype "bidirectional"))
    )
    (net (code "78") (name "Net-(C26-P$2)") (class "Default")
      (node (ref "C26") (pin "2") (pinfunction "P$2_2") (pintype "passive"))
      (node (ref "U14") (pin "P$1") (pinfunction "INTVCC_P$1") (pintype "bidirectional"))
    )
    (net (code "79") (name "Net-(C27-P$1)") (class "Default")
      (node (ref "C27") (pin "1") (pinfunction "P$1_1") (pintype "passive"))
      (node (ref "L3") (pin "P$2") (pinfunction "P$2_P$2") (pintype "passive"))
      (node (ref "U14") (pin "P$4") (pinfunction "SW_P$4") (pintype "bidirectional"))
    )
    (net (code "80") (name "Net-(C27-P$2)") (class "Default")
      (node (ref "C27") (pin "2") (pinfunction "P$2_2") (pintype "passive"))
      (node (ref "U14") (pin "P$2") (pinfunction "BOOST_P$2") (pintype "bidirectional"))
    )
    (net (code "81") (name "Net-(C29-P$2)") (class "Default")
      (node (ref "C29") (pin "2") (pinfunction "P$2_2") (pintype "passive"))
      (node (ref "R77") (pin "2") (pinfunction "2_2") (pintype "passive"))
      (node (ref "R78") (pin "2") (pinfunction "2_2") (pintype "passive"))
      (node (ref "SW1") (pin "P$2") (pinfunction "CNTRL_P$2") (pintype "input"))
    )
    (net (code "82") (name "Net-(C33-P$2)") (class "Default")
      (node (ref "C33") (pin "2") (pinfunction "P$2_2") (pintype "passive"))
      (node (ref "U16") (pin "P$1") (pinfunction "INTVCC_P$1") (pintype "bidirectional"))
    )
    (net (code "83") (name "Net-(C34-P$1)") (class "Default")
      (node (ref "C34") (pin "1") (pinfunction "P$1_1") (pintype "passive"))
      (node (ref "L4") (pin "P$2") (pinfunction "P$2_P$2") (pintype "passive"))
      (node (ref "U16") (pin "P$4") (pinfunction "SW_P$4") (pintype "bidirectional"))
    )
    (net (code "84") (name "Net-(C34-P$2)") (class "Default")
      (node (ref "C34") (pin "2") (pinfunction "P$2_2") (pintype "passive"))
      (node (ref "U16") (pin "P$2") (pinfunction "BOOST_P$2") (pintype "bidirectional"))
    )
    (net (code "85") (name "Net-(C36-P$2)") (class "Default")
      (node (ref "C36") (pin "2") (pinfunction "P$2_2") (pintype "passive"))
      (node (ref "R80") (pin "2") (pinfunction "2_2") (pintype "passive"))
      (node (ref "R81") (pin "2") (pinfunction "2_2") (pintype "passive"))
      (node (ref "SW2") (pin "P$2") (pinfunction "CNTRL_P$2") (pintype "input"))
    )
    (net (code "86") (name "Net-(LIFEPO41-PadMINUS)") (class "Default")
      (node (ref "LIFEPO41") (pin "MINUS") (pinfunction "MINUS_MINUS") (pintype "power_in"))
      (node (ref "LIFEPO42") (pin "PLUS") (pinfunction "PLUS_PLUS") (pintype "power_in"))
      (node (ref "R47") (pin "2") (pinfunction "2_2") (pintype "passive"))
    )
    (net (code "87") (name "Net-(LIFEPO43-PadMINUS)") (class "Default")
      (node (ref "LIFEPO43") (pin "MINUS") (pinfunction "MINUS_MINUS") (pintype "power_in"))
      (node (ref "LIFEPO44") (pin "PLUS") (pinfunction "PLUS_PLUS") (pintype "power_in"))
      (node (ref "R65") (pin "2") (pinfunction "2_2") (pintype "passive"))
    )
    (net (code "88") (name "Net-(M1-G)") (class "Default")
      (node (ref "M1") (pin "P$4") (pinfunction "G_P$4") (pintype "bidirectional"))
      (node (ref "U3") (pin "P$5") (pinfunction "GATE_P$5") (pintype "bidirectional"))
    )
    (net (code "89") (name "Net-(SW1-ISNS)") (class "Default")
      (node (ref "R58") (pin "2") (pinfunction "2_2") (pintype "passive"))
      (node (ref "R79") (pin "2") (pinfunction "2_2") (pintype "passive"))
      (node (ref "SW1") (pin "P$3") (pinfunction "ISNS_P$3") (pintype "output"))
    )
    (net (code "90") (name "Net-(SW2-ISNS)") (class "Default")
      (node (ref "R76") (pin "2") (pinfunction "2_2") (pintype "passive"))
      (node (ref "R82") (pin "2") (pinfunction "2_2") (pintype "passive"))
      (node (ref "SW2") (pin "P$3") (pinfunction "ISNS_P$3") (pintype "output"))
    )
    (net (code "91") (name "Net-(U1-P03)") (class "Default")
      (node (ref "R32") (pin "2") (pinfunction "2_2") (pintype "passive"))
      (node (ref "U1") (pin "P$7") (pinfunction "P03_P$7") (pintype "bidirectional"))
    )
    (net (code "92") (name "Net-(U1-P10)") (class "Default")
      (node (ref "R72") (pin "2") (pinfunction "2_2") (pintype "passive"))
      (node (ref "U1") (pin "P$13") (pinfunction "P10_P$13") (pintype "bidirectional"))
    )
    (net (code "93") (name "Net-(U1-P11)") (class "Default")
      (node (ref "R57") (pin "2") (pinfunction "2_2") (pintype "passive"))
      (node (ref "U1") (pin "P$14") (pinfunction "P11_P$14") (pintype "bidirectional"))
    )
    (net (code "94") (name "Net-(U1-P12)") (class "Default")
      (node (ref "R56") (pin "2") (pinfunction "2_2") (pintype "passive"))
      (node (ref "U1") (pin "P$15") (pinfunction "P12_P$15") (pintype "bidirectional"))
    )
    (net (code "95") (name "Net-(U1-P13)") (class "Default")
      (node (ref "R55") (pin "2") (pinfunction "2_2") (pintype "passive"))
      (node (ref "U1") (pin "P$16") (pinfunction "P13_P$16") (pintype "bidirectional"))
    )
    (net (code "96") (name "Net-(U4-CHGSNS)") (class "Default")
      (node (ref "L1") (pin "P$2") (pinfunction "P$2_P$2") (pintype "passive"))
      (node (ref "U4") (pin "P$8") (pinfunction "CHGSNS_P$8") (pintype "bidirectional"))
    )
    (net (code "97") (name "Net-(U4-MPPT)") (class "Default")
      (node (ref "R27") (pin "1") (pinfunction "1_1") (pintype "passive"))
      (node (ref "R28") (pin "2") (pinfunction "2_2") (pintype "passive"))
      (node (ref "U4") (pin "P$6") (pinfunction "MPPT_P$6") (pintype "bidirectional"))
    )
    (net (code "98") (name "Net-(U5-CHGSNS)") (class "Default")
      (node (ref "L2") (pin "P$2") (pinfunction "P$2_P$2") (pintype "passive"))
      (node (ref "U5") (pin "P$8") (pinfunction "CHGSNS_P$8") (pintype "bidirectional"))
    )
    (net (code "99") (name "Net-(U5-MPPT)") (class "Default")
      (node (ref "R10") (pin "1") (pinfunction "1_1") (pintype "passive"))
      (node (ref "R11") (pin "2") (pinfunction "2_2") (pintype "passive"))
      (node (ref "U5") (pin "P$6") (pinfunction "MPPT_P$6") (pintype "bidirectional"))
    )
    (net (code "100") (name "Net-(U6-CS)") (class "Default")
      (node (ref "R8") (pin "2") (pinfunction "2_2") (pintype "passive"))
      (node (ref "U6") (pin "P$2") (pinfunction "CS_P$2") (pintype "bidirectional"))
    )
    (net (code "101") (name "Net-(U6-S1)") (class "Default")
      (node (ref "U6") (pin "P$6") (pinfunction "S1_P$6") (pintype "bidirectional"))
      (node (ref "V23") (pin "P$1") (pinfunction "P$1_P$1") (pintype "bidirectional"))
    )
    (net (code "102") (name "Net-(U7-CS)") (class "Default")
      (node (ref "R23") (pin "2") (pinfunction "2_2") (pintype "passive"))
      (node (ref "U7") (pin "P$2") (pinfunction "CS_P$2") (pintype "bidirectional"))
    )
    (net (code "103") (name "Net-(U7-S1)") (class "Default")
      (node (ref "U7") (pin "P$6") (pinfunction "S1_P$6") (pintype "bidirectional"))
      (node (ref "V25") (pin "P$1") (pinfunction "P$1_P$1") (pintype "bidirectional"))
    )
    (net (code "104") (name "Net-(U8-VREF1)") (class "Default")
      (node (ref "R4") (pin "2") (pinfunction "2_2") (pintype "passive"))
      (node (ref "R6") (pin "1") (pinfunction "1_1") (pintype "passive"))
      (node (ref "U8") (pin "P$3") (pinfunction "VREF2_P$3") (pintype "bidirectional"))
      (node (ref "U8") (pin "P$7") (pinfunction "VREF1_P$7") (pintype "bidirectional"))
    )
    (net (code "105") (name "Net-(U9-VREF1)") (class "Default")
      (node (ref "R20") (pin "2") (pinfunction "2_2") (pintype "passive"))
      (node (ref "R21") (pin "1") (pinfunction "1_1") (pintype "passive"))
      (node (ref "U9") (pin "P$3") (pinfunction "VREF2_P$3") (pintype "bidirectional"))
      (node (ref "U9") (pin "P$7") (pinfunction "VREF1_P$7") (pintype "bidirectional"))
    )
    (net (code "106") (name "Net-(U14-CHGSNS)") (class "Default")
      (node (ref "L3") (pin "P$1") (pinfunction "P$1_P$1") (pintype "passive"))
      (node (ref "U14") (pin "P$8") (pinfunction "CHGSNS_P$8") (pintype "bidirectional"))
    )
    (net (code "107") (name "Net-(U14-FB)") (class "Default")
      (node (ref "R52") (pin "2") (pinfunction "2_2") (pintype "passive"))
      (node (ref "R53") (pin "1") (pinfunction "1_1") (pintype "passive"))
      (node (ref "U14") (pin "P$10") (pinfunction "FB_P$10") (pintype "bidirectional"))
    )
    (net (code "108") (name "Net-(U14-FBG)") (class "Default")
      (node (ref "R52") (pin "1") (pinfunction "1_1") (pintype "passive"))
      (node (ref "U14") (pin "P$11") (pinfunction "FBG_P$11") (pintype "bidirectional"))
    )
    (net (code "109") (name "Net-(U14-MPPT)") (class "Default")
      (node (ref "R45") (pin "1") (pinfunction "1_1") (pintype "passive"))
      (node (ref "R46") (pin "2") (pinfunction "2_2") (pintype "passive"))
      (node (ref "U14") (pin "P$6") (pinfunction "MPPT_P$6") (pintype "bidirectional"))
    )
    (net (code "110") (name "Net-(U14-PROG)") (class "Default")
      (node (ref "R51") (pin "1") (pinfunction "1_1") (pintype "passive"))
      (node (ref "U14") (pin "P$13") (pinfunction "PROG_P$13") (pintype "bidirectional"))
    )
    (net (code "111") (name "Net-(U16-CHGSNS)") (class "Default")
      (node (ref "L4") (pin "P$1") (pinfunction "P$1_P$1") (pintype "passive"))
      (node (ref "U16") (pin "P$8") (pinfunction "CHGSNS_P$8") (pintype "bidirectional"))
    )
    (net (code "112") (name "Net-(U16-FB)") (class "Default")
      (node (ref "R70") (pin "2") (pinfunction "2_2") (pintype "passive"))
      (node (ref "R71") (pin "1") (pinfunction "1_1") (pintype "passive"))
      (node (ref "U16") (pin "P$10") (pinfunction "FB_P$10") (pintype "bidirectional"))
    )
    (net (code "113") (name "Net-(U16-FBG)") (class "Default")
      (node (ref "R70") (pin "1") (pinfunction "1_1") (pintype "passive"))
      (node (ref "U16") (pin "P$11") (pinfunction "FBG_P$11") (pintype "bidirectional"))
    )
    (net (code "114") (name "Net-(U16-MPPT)") (class "Default")
      (node (ref "R63") (pin "1") (pinfunction "1_1") (pintype "passive"))
      (node (ref "R64") (pin "2") (pinfunction "2_2") (pintype "passive"))
      (node (ref "U16") (pin "P$6") (pinfunction "MPPT_P$6") (pintype "bidirectional"))
    )
    (net (code "115") (name "Net-(U16-PROG)") (class "Default")
      (node (ref "R69") (pin "1") (pinfunction "1_1") (pintype "passive"))
      (node (ref "U16") (pin "P$13") (pinfunction "PROG_P$13") (pintype "bidirectional"))
    )
    (net (code "116") (name "Net-(U18-VREF1)") (class "Default")
      (node (ref "R24") (pin "2") (pinfunction "2_2") (pintype "passive"))
      (node (ref "R26") (pin "1") (pinfunction "1_1") (pintype "passive"))
      (node (ref "U18") (pin "P$3") (pinfunction "VREF2_P$3") (pintype "bidirectional"))
      (node (ref "U18") (pin "P$7") (pinfunction "VREF1_P$7") (pintype "bidirectional"))
    )
    (net (code "117") (name "Net-(U19-VREF1)") (class "Default")
      (node (ref "R29") (pin "2") (pinfunction "2_2") (pintype "passive"))
      (node (ref "R30") (pin "1") (pinfunction "1_1") (pintype "passive"))
      (node (ref "U19") (pin "P$3") (pinfunction "VREF2_P$3") (pintype "bidirectional"))
      (node (ref "U19") (pin "P$7") (pinfunction "VREF1_P$7") (pintype "bidirectional"))
    )
    (net (code "118") (name "PANELREF") (class "Default")
      (node (ref "C43") (pin "1") (pinfunction "P$1_1") (pintype "passive"))
      (node (ref "R13") (pin "1") (pinfunction "1_1") (pintype "passive"))
      (node (ref "R14") (pin "2") (pinfunction "2_2") (pintype "passive"))
      (node (ref "U2") (pin "P$6") (pinfunction "VIN3/REF_P$6") (pintype "bidirectional"))
    )
    (net (code "119") (name "SCL") (class "Default")
      (node (ref "R85") (pin "1") (pinfunction "1_1") (pintype "passive"))
      (node (ref "U1") (pin "P$22") (pinfunction "SCL_P$22") (pintype "bidirectional"))
      (node (ref "U2") (pin "P$1") (pinfunction "SCL_P$1") (pintype "bidirectional"))
      (node (ref "V5") (pin "P$1") (pinfunction "P$1_P$1") (pintype "bidirectional"))
    )
    (net (code "120") (name "SDA") (class "Default")
      (node (ref "R86") (pin "1") (pinfunction "1_1") (pintype "passive"))
      (node (ref "U1") (pin "P$23") (pinfunction "SDA_P$23") (pintype "bidirectional"))
      (node (ref "U2") (pin "P$2") (pinfunction "SDA_P$2") (pintype "bidirectional"))
      (node (ref "V6") (pin "P$1") (pinfunction "P$1_P$1") (pintype "bidirectional"))
    )
    (net (code "121") (name "SPF_ST") (class "Default")
      (node (ref "R83") (pin "1") (pinfunction "1_1") (pintype "passive"))
      (node (ref "U1") (pin "P$6") (pinfunction "P02_P$6") (pintype "bidirectional"))
      (node (ref "U3") (pin "P$4") (pinfunction "STAT_P$4") (pintype "bidirectional"))
    )
    (net (code "122") (name "SP_C") (class "Default")
      (node (ref "C3") (pin "1") (pinfunction "P$1_1") (pintype "passive"))
      (node (ref "M1") (pin "P$5") (pinfunction "D_P$5") (pintype "bidirectional"))
      (node (ref "M1") (pin "P$6") (pinfunction "D_P$6") (pintype "bidirectional"))
      (node (ref "M1") (pin "P$7") (pinfunction "D_P$7") (pintype "bidirectional"))
      (node (ref "M1") (pin "P$8") (pinfunction "D_P$8") (pintype "bidirectional"))
      (node (ref "U3") (pin "P$1") (pinfunction "VIN_P$1") (pintype "bidirectional"))
      (node (ref "V13") (pin "P$1") (pinfunction "P$1_P$1") (pintype "bidirectional"))
      (node (ref "V14") (pin "P$1") (pinfunction "P$1_P$1") (pintype "bidirectional"))
      (node (ref "V15") (pin "P$1") (pinfunction "P$1_P$1") (pintype "bidirectional"))
      (node (ref "V16") (pin "P$1") (pinfunction "P$1_P$1") (pintype "bidirectional"))
      (node (ref "V17") (pin "P$1") (pinfunction "P$1_P$1") (pintype "bidirectional"))
      (node (ref "V18") (pin "P$1") (pinfunction "P$1_P$1") (pintype "bidirectional"))
    )
    (net (code "123") (name "SP_OUT") (class "Default")
      (node (ref "C17") (pin "1") (pinfunction "P$1_1") (pintype "passive"))
      (node (ref "C18") (pin "1") (pinfunction "P$1_1") (pintype "passive"))
      (node (ref "C4") (pin "1") (pinfunction "P$1_1") (pintype "passive"))
      (node (ref "D1") (pin "C") (pinfunction "C_C") (pintype "bidirectional"))
      (node (ref "D6") (pin "A") (pinfunction "A_A") (pintype "bidirectional"))
      (node (ref "D7") (pin "A") (pinfunction "A_A") (pintype "bidirectional"))
      (node (ref "D8") (pin "A") (pinfunction "A_A") (pintype "bidirectional"))
      (node (ref "D9") (pin "A") (pinfunction "A_A") (pintype "bidirectional"))
      (node (ref "M1") (pin "P$1") (pinfunction "S_P$1") (pintype "bidirectional"))
      (node (ref "M1") (pin "P$2") (pinfunction "S_P$2") (pintype "bidirectional"))
      (node (ref "M1") (pin "P$3") (pinfunction "S_P$3") (pintype "bidirectional"))
      (node (ref "R13") (pin "2") (pinfunction "2_2") (pintype "passive"))
      (node (ref "U10") (pin "P$5") (pinfunction "~{SHDN}_P$5") (pintype "bidirectional"))
      (node (ref "U10") (pin "P$8") (pinfunction "IN_P$8") (pintype "bidirectional"))
      (node (ref "U11") (pin "P$5") (pinfunction "~{SHDN}_P$5") (pintype "bidirectional"))
      (node (ref "U11") (pin "P$8") (pinfunction "IN_P$8") (pintype "bidirectional"))
      (node (ref "U3") (pin "P$6") (pinfunction "SNS_P$6") (pintype "bidirectional"))
    )
    (net (code "124") (name "UMB_CHG") (class "Default")
      (node (ref "D1") (pin "A") (pinfunction "A_A") (pintype "bidirectional"))
      (node (ref "V19") (pin "P$1") (pinfunction "P$1_P$1") (pintype "bidirectional"))
    )
    (net (code "125") (name "~{BATT_INT}") (class "Default")
      (node (ref "R84") (pin "1") (pinfunction "1_1") (pintype "passive"))
      (node (ref "U1") (pin "P$1") (pinfunction "~{INT}_P$1") (pintype "bidirectional"))
    )
  )
)
